# DIO-SMA.net
KiCad netlist of a schematic drawn in Altium Designer
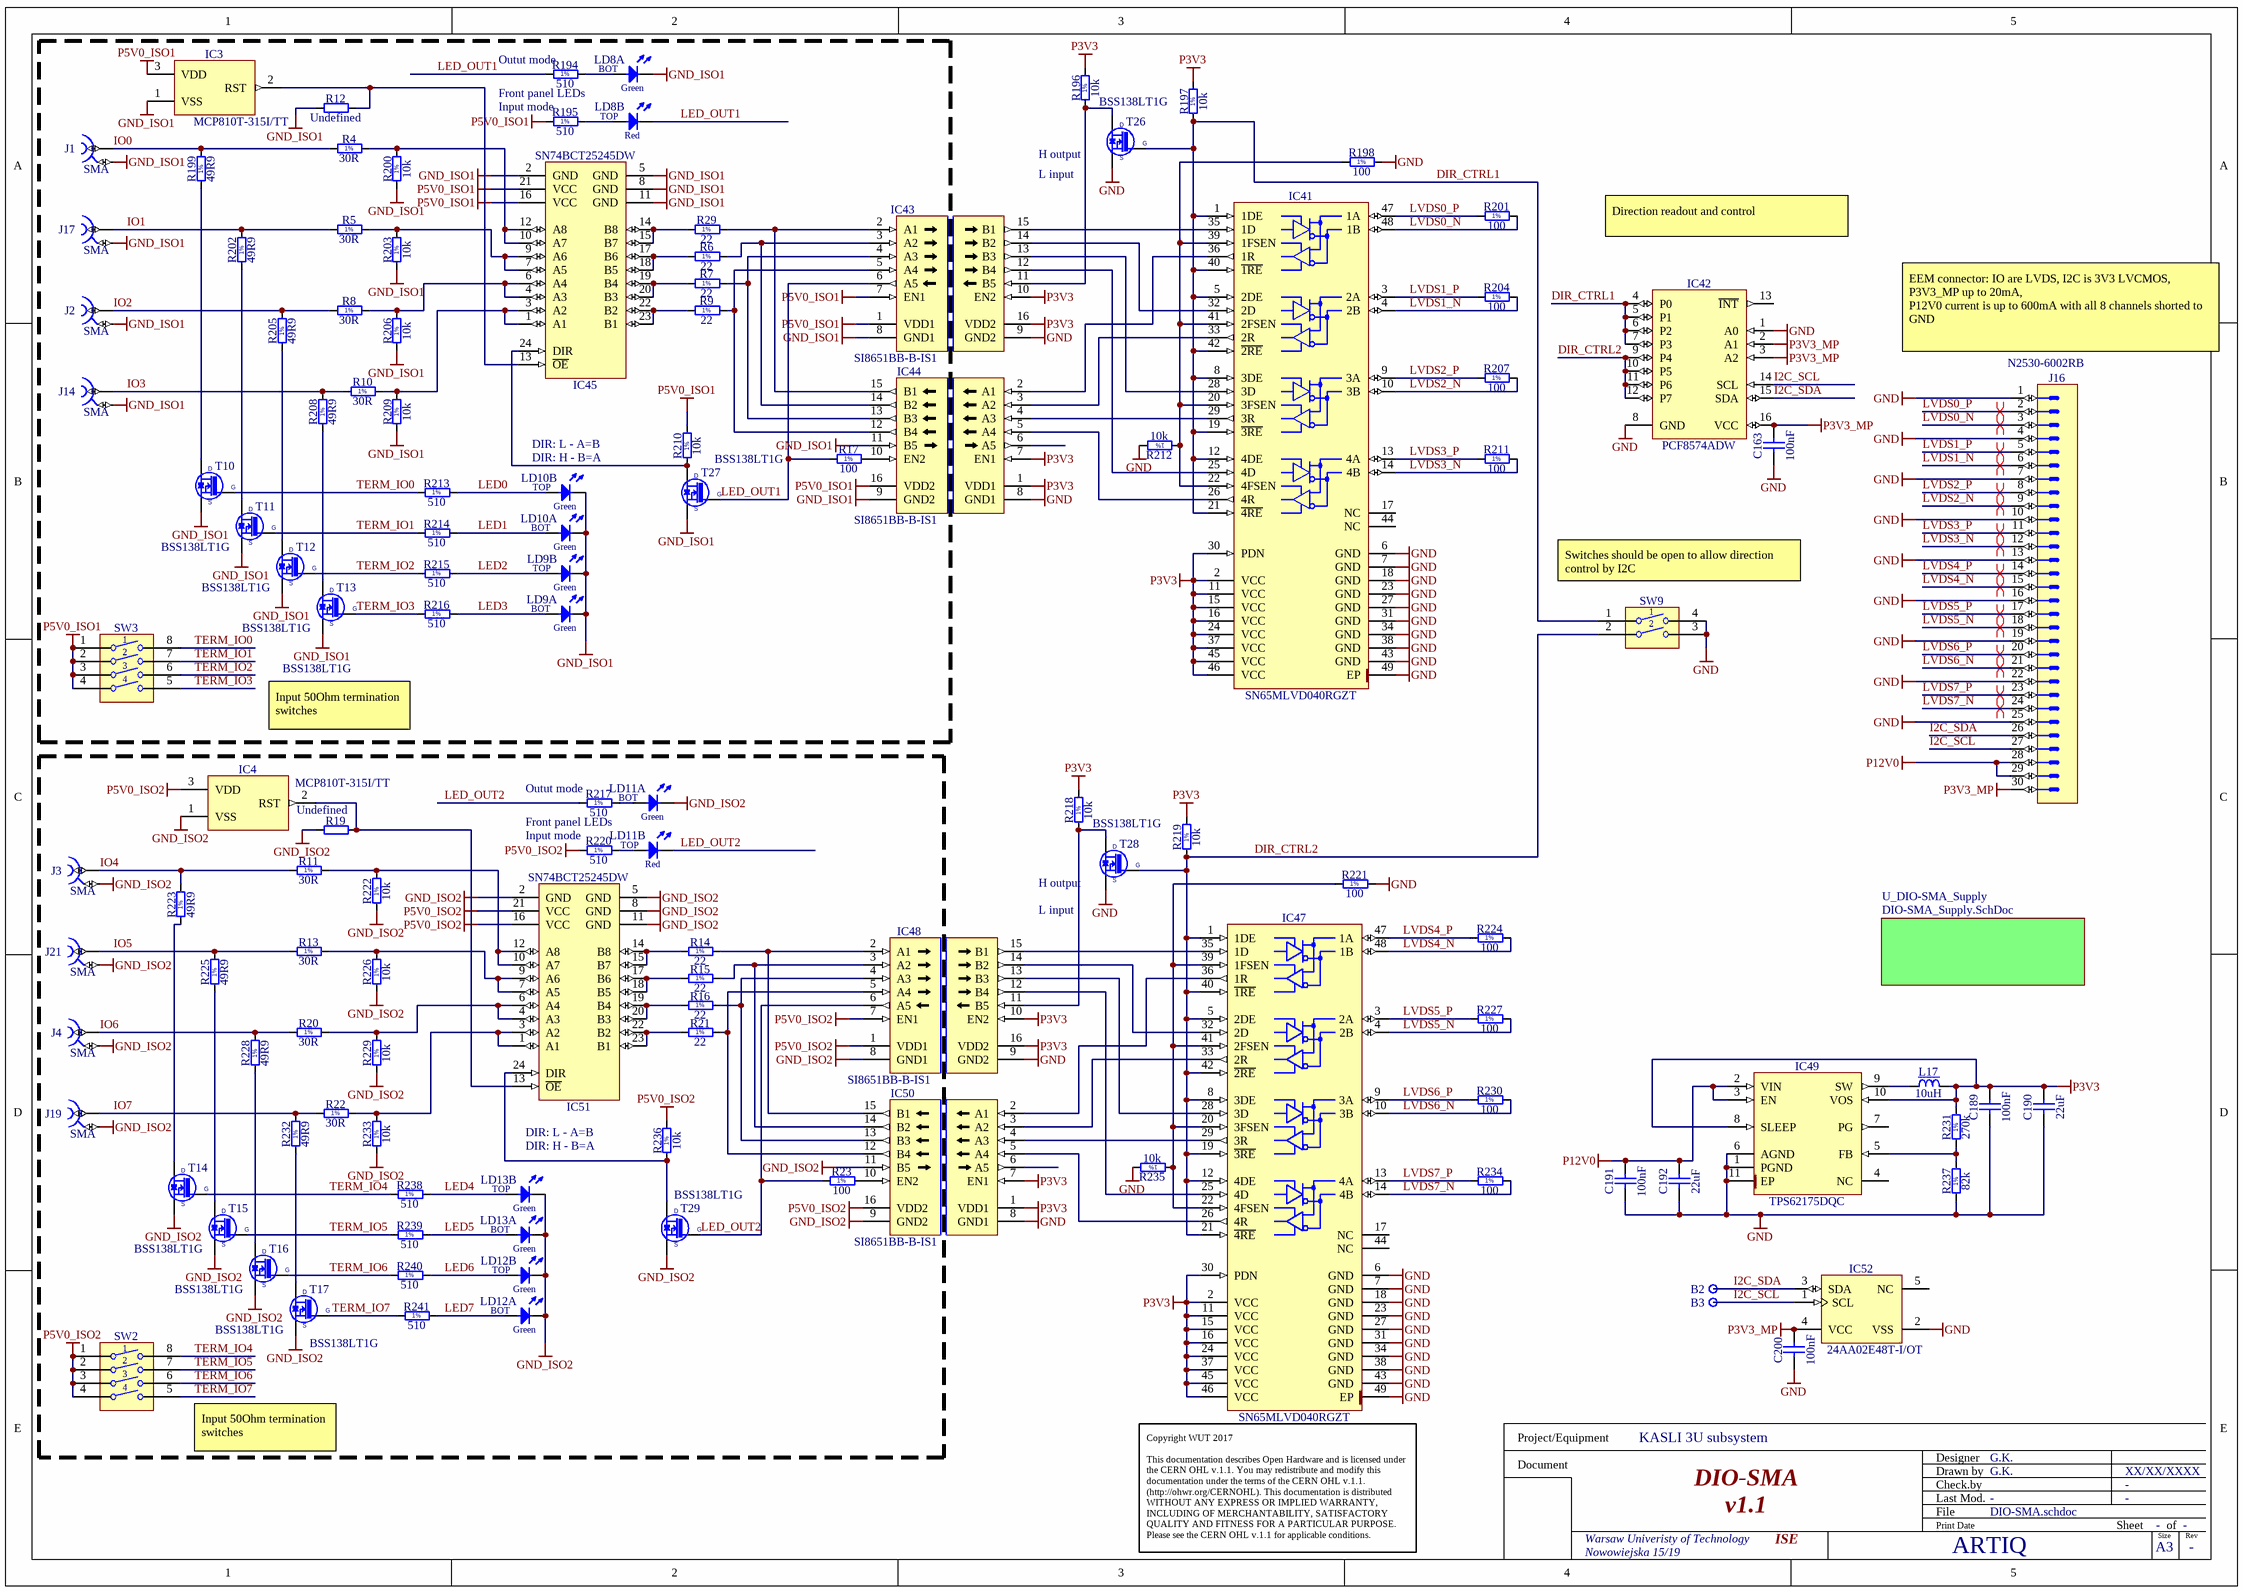
[diagram p0: DIO-SMA.schdoc]

(export (version "E")
  (design (tool "Eeschema 10.0.6"))
  (components
    (comp (ref "B2")
      (value "Plated Hole")
      (footprint "c130h60")
      (description "Single Terminal Socket")
      (fields (field (name "PART NUMBER") "PLATED_HOLE0.6_PAD1.3") (field (name "AUTHOR") "CERN DEM MR"))
      (libsource (lib "Eletro-mechanical") (part "Single Terminal Socket"))
    )
    (comp (ref "B3")
      (value "Plated Hole")
      (footprint "c130h60")
      (description "Single Terminal Socket")
      (fields (field (name "PART NUMBER") "PLATED_HOLE0.6_PAD1.3") (field (name "AUTHOR") "CERN DEM MR"))
      (libsource (lib "Eletro-mechanical") (part "Single Terminal Socket"))
    )
    (comp (ref "C163")
      (value "100nF")
      (footprint "CAPC1005X55N")
      (description "Non-polarised capacitor")
      (fields
        (field (name "PART NUMBER") "CC0402_100NF_16V_10%_X5R")
        (field (name "VOLTAGE") "16V")
        (field (name "AUTHOR") "CERN DEM JLC")
      )
      (libsource (lib "Capacitors") (part "Capacitor - non polarized"))
    )
    (comp (ref "C189")
      (value "100nF")
      (footprint "CAPC1005X55N")
      (description "Non-polarised capacitor")
      (fields
        (field (name "PART NUMBER") "CC0402_100NF_16V_10%_X5R")
        (field (name "VOLTAGE") "16V")
        (field (name "AUTHOR") "CERN DEM JLC")
      )
      (libsource (lib "Capacitors") (part "Capacitor - non polarized"))
    )
    (comp (ref "C190")
      (value "22uF")
      (footprint "CAPC2012X135N")
      (description "Non-polarised capacitor")
      (fields
        (field (name "PART NUMBER") "CC0805_22UF_16V_10%_X5R")
        (field (name "VOLTAGE") "16V")
        (field (name "AUTHOR") "CERN DEM JLC")
      )
      (libsource (lib "Capacitors") (part "Capacitor - non polarized"))
    )
    (comp (ref "C191")
      (value "100nF")
      (footprint "CAPC1005X55N")
      (description "Non-polarised capacitor")
      (fields
        (field (name "PART NUMBER") "CC0402_100NF_16V_10%_X5R")
        (field (name "VOLTAGE") "16V")
        (field (name "AUTHOR") "CERN DEM JLC")
      )
      (libsource (lib "Capacitors") (part "Capacitor - non polarized"))
    )
    (comp (ref "C192")
      (value "22uF")
      (footprint "CAPC2012X135N")
      (description "Non-polarised capacitor")
      (fields
        (field (name "PART NUMBER") "CC0805_22UF_16V_10%_X5R")
        (field (name "VOLTAGE") "16V")
        (field (name "AUTHOR") "CERN DEM JLC")
      )
      (libsource (lib "Capacitors") (part "Capacitor - non polarized"))
    )
    (comp (ref "C200")
      (value "100nF")
      (footprint "CAPC1005X55N")
      (description "Non-polarised capacitor")
      (fields
        (field (name "PART NUMBER") "CC0402_100NF_16V_10%_X5R")
        (field (name "VOLTAGE") "16V")
        (field (name "AUTHOR") "CERN DEM JLC")
      )
      (libsource (lib "Capacitors") (part "Capacitor - non polarized"))
    )
    (comp (ref "IC3")
      (value "MCP810T-315I/TT")
      (footprint "SOT95P237X112-3N")
      (description "3.075V Microcontroller Supervisory Circuit With Push-Pull Output")
      (fields (field (name "MANUFACTURER") "MICROCHIP TECHNOLOGY") (field (name "AUTHOR") "GK"))
      (libsource (lib "LIBRARY_SCH") (part "VMON_MCP810"))
    )
    (comp (ref "IC4")
      (value "MCP810T-315I/TT")
      (footprint "SOT95P237X112-3N")
      (description "3.075V Microcontroller Supervisory Circuit With Push-Pull Output")
      (fields (field (name "MANUFACTURER") "MICROCHIP TECHNOLOGY") (field (name "AUTHOR") "GK"))
      (libsource (lib "LIBRARY_SCH") (part "VMON_MCP810"))
    )
    (comp (ref "IC41")
      (value "SN65MLVD040RGZT")
      (footprint "QFN50P700X700X100-49N-S420")
      (description "4-Channel Half-Duplex M-LVDS Line Transceiver")
      (fields (field (name "MANUFACTURER") "TEXAS INSTRUMENTS") (field (name "AUTHOR") "CERN DEM JLC"))
      (libsource (lib "ICs And Semiconductors") (part "SN65MLVD040"))
    )
    (comp (ref "IC42")
      (value "PCF8574ADW")
      (footprint "SOIC127P1030X265-16N")
      (description "Remote 8-bit I/O Expander For I2C Bus")
      (fields (field (name "MANUFACTURER") "TEXAS INSTRUMENTS") (field (name "AUTHOR") "CERN DEM JLC"))
      (libsource (lib "ICs And Semiconductors") (part "PCF8574ADW"))
    )
    (comp (ref "IC43")
      (value "SI8651BB-B-IS1")
      (footprint "SOIC127P600X175-16N")
      (description "Low Power Five-Channel Digital Isolator")
      (fields (field (name "MANUFACTURER") "SILICON LABS") (field (name "AUTHOR") "CERN DEM JLC"))
      (libsource (lib "ICs And Semiconductors") (part "Si8651"))
    )
    (comp (ref "IC44")
      (value "SI8651BB-B-IS1")
      (footprint "SOIC127P600X175-16N")
      (description "Low Power Five-Channel Digital Isolator")
      (fields (field (name "MANUFACTURER") "SILICON LABS") (field (name "AUTHOR") "CERN DEM JLC"))
      (libsource (lib "") (part "Si8651_1"))
    )
    (comp (ref "IC45")
      (value "SN74BCT25245DW")
      (footprint "SOIC127P1030X265-24N")
      (description "25 Ohms Octal Bus Transceiver With 3-State Outputs")
      (fields (field (name "MANUFACTURER") "TEXAS INSTRUMENTS") (field (name "AUTHOR") "CERN DEM JLC"))
      (libsource (lib "ICs And Semiconductors") (part "7425245"))
    )
    (comp (ref "IC47")
      (value "SN65MLVD040RGZT")
      (footprint "QFN50P700X700X100-49N-S420")
      (description "4-Channel Half-Duplex M-LVDS Line Transceiver")
      (fields (field (name "MANUFACTURER") "TEXAS INSTRUMENTS") (field (name "AUTHOR") "CERN DEM JLC"))
      (libsource (lib "ICs And Semiconductors") (part "SN65MLVD040"))
    )
    (comp (ref "IC48")
      (value "SI8651BB-B-IS1")
      (footprint "SOIC127P600X175-16N")
      (description "Low Power Five-Channel Digital Isolator")
      (fields (field (name "MANUFACTURER") "SILICON LABS") (field (name "AUTHOR") "CERN DEM JLC"))
      (libsource (lib "ICs And Semiconductors") (part "Si8651"))
    )
    (comp (ref "IC49")
      (value "TPS62175DQC")
      (footprint "SON50P200X300X80-11N-R94X250")
      (description "4.75-28VDC to 1-6VDC, 500mA Step-Down Converter With Sleep Mode")
      (fields (field (name "MANUFACTURER") "TEXAS INSTRUMENTS") (field (name "AUTHOR") "CERN DEM JMW"))
      (libsource (lib "ICs And Semiconductors") (part "TPS62175"))
    )
    (comp (ref "IC50")
      (value "SI8651BB-B-IS1")
      (footprint "SOIC127P600X175-16N")
      (description "Low Power Five-Channel Digital Isolator")
      (fields (field (name "MANUFACTURER") "SILICON LABS") (field (name "AUTHOR") "CERN DEM JLC"))
      (libsource (lib "") (part "Si8651_1"))
    )
    (comp (ref "IC51")
      (value "SN74BCT25245DW")
      (footprint "SOIC127P1030X265-24N")
      (description "25 Ohms Octal Bus Transceiver With 3-State Outputs")
      (fields (field (name "MANUFACTURER") "TEXAS INSTRUMENTS") (field (name "AUTHOR") "CERN DEM JLC"))
      (libsource (lib "ICs And Semiconductors") (part "7425245"))
    )
    (comp (ref "IC52")
      (value "24AA02E48T-I/OT")
      (footprint "SOT95P280X145-5N")
      (description "1.7V-5.5V, 2K I2C Serial EEPROM With EUI-48 Node Identity")
      (fields (field (name "MANUFACTURER") "MICROCHIP TECHNOLOGY") (field (name "AUTHOR") "CERN DEM MR"))
      (libsource (lib "ICs And Semiconductors") (part "24AA02E48T-I/OT"))
    )
    (comp (ref "J1")
      (value "SMA")
      (footprint "RF249BT0050GHDW")
      (description "50 Ohm Through Hole SMA Right Angle PCB Jack")
      (fields
        (field (name "PART NUMBER") "AdamTech_RF249BT0050GHDW")
        (field (name "MANUFACTURER") "AdamTech")
        (field (name "AUTHOR") "GK")
      )
      (libsource (lib "LIBRARY_SCH") (part "CON_SMA_RF249BT0050GHDW"))
    )
    (comp (ref "J2")
      (value "SMA")
      (footprint "RF249BT0050GHDW")
      (description "50 Ohm Through Hole SMA Right Angle PCB Jack")
      (fields
        (field (name "PART NUMBER") "AdamTech_RF249BT0050GHDW")
        (field (name "MANUFACTURER") "AdamTech")
        (field (name "AUTHOR") "GK")
      )
      (libsource (lib "LIBRARY_SCH") (part "CON_SMA_RF249BT0050GHDW"))
    )
    (comp (ref "J3")
      (value "SMA")
      (footprint "RF249BT0050GHDW")
      (description "50 Ohm Through Hole SMA Right Angle PCB Jack")
      (fields
        (field (name "PART NUMBER") "AdamTech_RF249BT0050GHDW")
        (field (name "MANUFACTURER") "AdamTech")
        (field (name "AUTHOR") "GK")
      )
      (libsource (lib "LIBRARY_SCH") (part "CON_SMA_RF249BT0050GHDW"))
    )
    (comp (ref "J4")
      (value "SMA")
      (footprint "RF249BT0050GHDW")
      (description "50 Ohm Through Hole SMA Right Angle PCB Jack")
      (fields
        (field (name "PART NUMBER") "AdamTech_RF249BT0050GHDW")
        (field (name "MANUFACTURER") "AdamTech")
        (field (name "AUTHOR") "GK")
      )
      (libsource (lib "LIBRARY_SCH") (part "CON_SMA_RF249BT0050GHDW"))
    )
    (comp (ref "J14")
      (value "SMA")
      (footprint "MOLEX_73251-2120")
      (description "50 Ohm, SMA Edge Mount PCB, With Jam Nut And Lock Washer")
      (fields
        (field (name "PART NUMBER") "MOLEX_73251-2120")
        (field (name "MANUFACTURER") "MOLEX")
        (field (name "AUTHOR") "CERN DEM JLC")
      )
      (libsource (lib "LIBRARY_SCH") (part "CON_SMA_RA_SMD_73251-2120"))
    )
    (comp (ref "J16")
      (value "~")
      (footprint "3M_N2530-6002RB")
      (description "Connector 30 Male")
      (fields
        (field (name "PART NUMBER") "3M_N2530-6002RB")
        (field (name "MANUFACTURER") "3M")
        (field (name "MANUFACTURER PART NUMBER") "N2530-6002RB")
        (field (name "AUTHOR") "CERN DEM JLC")
      )
      (libsource (lib "Connectors") (part "Connector 30 Male"))
    )
    (comp (ref "J17")
      (value "SMA")
      (footprint "MOLEX_73251-2120")
      (description "50 Ohm, SMA Edge Mount PCB, With Jam Nut And Lock Washer")
      (fields
        (field (name "PART NUMBER") "MOLEX_73251-2120")
        (field (name "MANUFACTURER") "MOLEX")
        (field (name "AUTHOR") "CERN DEM JLC")
      )
      (libsource (lib "LIBRARY_SCH") (part "CON_SMA_RA_SMD_73251-2120"))
    )
    (comp (ref "J19")
      (value "SMA")
      (footprint "MOLEX_73251-2120")
      (description "50 Ohm, SMA Edge Mount PCB, With Jam Nut And Lock Washer")
      (fields
        (field (name "PART NUMBER") "MOLEX_73251-2120")
        (field (name "MANUFACTURER") "MOLEX")
        (field (name "AUTHOR") "CERN DEM JLC")
      )
      (libsource (lib "LIBRARY_SCH") (part "CON_SMA_RA_SMD_73251-2120"))
    )
    (comp (ref "J21")
      (value "SMA")
      (footprint "MOLEX_73251-2120")
      (description "50 Ohm, SMA Edge Mount PCB, With Jam Nut And Lock Washer")
      (fields
        (field (name "PART NUMBER") "MOLEX_73251-2120")
        (field (name "MANUFACTURER") "MOLEX")
        (field (name "AUTHOR") "CERN DEM JLC")
      )
      (libsource (lib "LIBRARY_SCH") (part "CON_SMA_RA_SMD_73251-2120"))
    )
    (comp (ref "L17")
      (value "10uH")
      (footprint "IND_MURATA-PS_8400")
      (description "Inductor With Core")
      (fields
        (field (name "PART NUMBER") "IND_10UH_10%_MURATA-PS_8400")
        (field (name "POWER") "950mA")
        (field (name "AUTHOR") "CERN DEM JLC")
      )
      (libsource (lib "Inductors & Transformers") (part "Inductor With Magnetic core"))
    )
    (comp (ref "LD8")
      (value "Red/Green")
      (footprint "LED_DIALIGHT_571-0112F")
      (description "2x LED  Botom Green, Top Red")
      (fields
        (field (name "PART NUMBER") "LED_DIALIGHT_571-0112F")
        (field (name "MANUFACTURER") "DIALIGHT")
        (field (name "AUTHOR") "CERN DEM JLC")
      )
      (libsource (lib "ICs And Semiconductors") (part "LED x2 G-1C2A-BOT_R-3C4A-TOP"))
    )
    (comp (ref "LD9")
      (value "Green/Green")
      (footprint "LED_DIALIGHT_571-0122F")
      (description "LED x2 Green 1C2A-BOT_3C4A-TOP")
      (fields
        (field (name "PART NUMBER") "LED_DIALIGHT_571-0122F")
        (field (name "MANUFACTURER") "DIALIGHT")
        (field (name "AUTHOR") "CERN DEM JLC")
      )
      (libsource (lib "ICs And Semiconductors") (part "LED x2 Green 1C2A-BOT_3C4A-TOP"))
    )
    (comp (ref "LD10")
      (value "Green/Green")
      (footprint "LED_DIALIGHT_571-0122F")
      (description "LED x2 Green 1C2A-BOT_3C4A-TOP")
      (fields
        (field (name "PART NUMBER") "LED_DIALIGHT_571-0122F")
        (field (name "MANUFACTURER") "DIALIGHT")
        (field (name "AUTHOR") "CERN DEM JLC")
      )
      (libsource (lib "ICs And Semiconductors") (part "LED x2 Green 1C2A-BOT_3C4A-TOP"))
    )
    (comp (ref "LD11")
      (value "Red/Green")
      (footprint "LED_DIALIGHT_571-0112F")
      (description "2x LED  Botom Green, Top Red")
      (fields
        (field (name "PART NUMBER") "LED_DIALIGHT_571-0112F")
        (field (name "MANUFACTURER") "DIALIGHT")
        (field (name "AUTHOR") "CERN DEM JLC")
      )
      (libsource (lib "ICs And Semiconductors") (part "LED x2 G-1C2A-BOT_R-3C4A-TOP"))
    )
    (comp (ref "LD12")
      (value "Green/Green")
      (footprint "LED_DIALIGHT_571-0122F")
      (description "LED x2 Green 1C2A-BOT_3C4A-TOP")
      (fields
        (field (name "PART NUMBER") "LED_DIALIGHT_571-0122F")
        (field (name "MANUFACTURER") "DIALIGHT")
        (field (name "AUTHOR") "CERN DEM JLC")
      )
      (libsource (lib "ICs And Semiconductors") (part "LED x2 Green 1C2A-BOT_3C4A-TOP"))
    )
    (comp (ref "LD13")
      (value "Green/Green")
      (footprint "LED_DIALIGHT_571-0122F")
      (description "LED x2 Green 1C2A-BOT_3C4A-TOP")
      (fields
        (field (name "PART NUMBER") "LED_DIALIGHT_571-0122F")
        (field (name "MANUFACTURER") "DIALIGHT")
        (field (name "AUTHOR") "CERN DEM JLC")
      )
      (libsource (lib "ICs And Semiconductors") (part "LED x2 Green 1C2A-BOT_3C4A-TOP"))
    )
    (comp (ref "R4")
      (value "30R")
      (footprint "RESC3225X70N")
      (description "Resistor - 5%")
      (fields
        (field (name "PART NUMBER") "R1210_30R_5%_0.5W_200ppm")
        (field (name "POWER") "0.5W")
        (field (name "AUTHOR") "CERN DEM JMW")
      )
      (libsource (lib "LIBRARY_SCH") (part "R1210_30R_5%_0.5W_200PPM"))
    )
    (comp (ref "R5")
      (value "30R")
      (footprint "RESC3225X70N")
      (description "Resistor - 5%")
      (fields
        (field (name "PART NUMBER") "R1210_30R_5%_0.5W_200ppm")
        (field (name "POWER") "0.5W")
        (field (name "AUTHOR") "CERN DEM JMW")
      )
      (libsource (lib "LIBRARY_SCH") (part "R1210_30R_5%_0.5W_200PPM"))
    )
    (comp (ref "R6")
      (value "22")
      (footprint "RESC1005X40N")
      (description "Resistor - 1%")
      (fields
        (field (name "PART NUMBER") "R0402_22R_1%_0.0625W_100PPM")
        (field (name "POWER") "0.0625W")
        (field (name "AUTHOR") "CERN DEM JLC")
      )
      (libsource (lib "Resistors") (part "Resistor - 1%"))
    )
    (comp (ref "R7")
      (value "22")
      (footprint "RESC1005X40N")
      (description "Resistor - 1%")
      (fields
        (field (name "PART NUMBER") "R0402_22R_1%_0.0625W_100PPM")
        (field (name "POWER") "0.0625W")
        (field (name "AUTHOR") "CERN DEM JLC")
      )
      (libsource (lib "Resistors") (part "Resistor - 1%"))
    )
    (comp (ref "R8")
      (value "30R")
      (footprint "RESC3225X70N")
      (description "Resistor - 5%")
      (fields
        (field (name "PART NUMBER") "R1210_30R_5%_0.5W_200ppm")
        (field (name "POWER") "0.5W")
        (field (name "AUTHOR") "CERN DEM JMW")
      )
      (libsource (lib "LIBRARY_SCH") (part "R1210_30R_5%_0.5W_200PPM"))
    )
    (comp (ref "R9")
      (value "22")
      (footprint "RESC1005X40N")
      (description "Resistor - 1%")
      (fields
        (field (name "PART NUMBER") "R0402_22R_1%_0.0625W_100PPM")
        (field (name "POWER") "0.0625W")
        (field (name "AUTHOR") "CERN DEM JLC")
      )
      (libsource (lib "Resistors") (part "Resistor - 1%"))
    )
    (comp (ref "R10")
      (value "30R")
      (footprint "RESC3225X70N")
      (description "Resistor - 5%")
      (fields
        (field (name "PART NUMBER") "R1210_30R_5%_0.5W_200ppm")
        (field (name "POWER") "0.5W")
        (field (name "AUTHOR") "CERN DEM JMW")
      )
      (libsource (lib "LIBRARY_SCH") (part "R1210_30R_5%_0.5W_200PPM"))
    )
    (comp (ref "R11")
      (value "30R")
      (footprint "RESC3225X70N")
      (description "Resistor - 5%")
      (fields
        (field (name "PART NUMBER") "R1210_30R_5%_0.5W_200ppm")
        (field (name "POWER") "0.5W")
        (field (name "AUTHOR") "CERN DEM JMW")
      )
      (libsource (lib "LIBRARY_SCH") (part "R1210_30R_5%_0.5W_200PPM"))
    )
    (comp (ref "R12")
      (value "Undefined")
      (footprint "RESC1005X40N")
      (description "Resistor")
      (fields (field (name "PART NUMBER") "R0402_NO-VALUE") (field (name "AUTHOR") "CERN DEM JLC"))
      (libsource (lib "Resistors") (part "Resistor"))
    )
    (comp (ref "R13")
      (value "30R")
      (footprint "RESC3225X70N")
      (description "Resistor - 5%")
      (fields
        (field (name "PART NUMBER") "R1210_30R_5%_0.5W_200ppm")
        (field (name "POWER") "0.5W")
        (field (name "AUTHOR") "CERN DEM JMW")
      )
      (libsource (lib "LIBRARY_SCH") (part "R1210_30R_5%_0.5W_200PPM"))
    )
    (comp (ref "R14")
      (value "22")
      (footprint "RESC1005X40N")
      (description "Resistor - 1%")
      (fields
        (field (name "PART NUMBER") "R0402_22R_1%_0.0625W_100PPM")
        (field (name "POWER") "0.0625W")
        (field (name "AUTHOR") "CERN DEM JLC")
      )
      (libsource (lib "Resistors") (part "Resistor - 1%"))
    )
    (comp (ref "R15")
      (value "22")
      (footprint "RESC1005X40N")
      (description "Resistor - 1%")
      (fields
        (field (name "PART NUMBER") "R0402_22R_1%_0.0625W_100PPM")
        (field (name "POWER") "0.0625W")
        (field (name "AUTHOR") "CERN DEM JLC")
      )
      (libsource (lib "Resistors") (part "Resistor - 1%"))
    )
    (comp (ref "R16")
      (value "22")
      (footprint "RESC1005X40N")
      (description "Resistor - 1%")
      (fields
        (field (name "PART NUMBER") "R0402_22R_1%_0.0625W_100PPM")
        (field (name "POWER") "0.0625W")
        (field (name "AUTHOR") "CERN DEM JLC")
      )
      (libsource (lib "Resistors") (part "Resistor - 1%"))
    )
    (comp (ref "R17")
      (value "100")
      (footprint "RESC1005X40N")
      (description "Resistor - 1%")
      (fields
        (field (name "PART NUMBER") "R0402_100R_1%_0.1W_100PPM")
        (field (name "POWER") "0.1W")
        (field (name "AUTHOR") "CERN DEM JLC")
      )
      (libsource (lib "Resistors") (part "Resistor - 1%"))
    )
    (comp (ref "R19")
      (value "Undefined")
      (footprint "RESC1005X40N")
      (description "Resistor")
      (fields (field (name "PART NUMBER") "R0402_NO-VALUE") (field (name "AUTHOR") "CERN DEM JLC"))
      (libsource (lib "Resistors") (part "Resistor"))
    )
    (comp (ref "R20")
      (value "30R")
      (footprint "RESC3225X70N")
      (description "Resistor - 5%")
      (fields
        (field (name "PART NUMBER") "R1210_30R_5%_0.5W_200ppm")
        (field (name "POWER") "0.5W")
        (field (name "AUTHOR") "CERN DEM JMW")
      )
      (libsource (lib "LIBRARY_SCH") (part "R1210_30R_5%_0.5W_200PPM"))
    )
    (comp (ref "R21")
      (value "22")
      (footprint "RESC1005X40N")
      (description "Resistor - 1%")
      (fields
        (field (name "PART NUMBER") "R0402_22R_1%_0.0625W_100PPM")
        (field (name "POWER") "0.0625W")
        (field (name "AUTHOR") "CERN DEM JLC")
      )
      (libsource (lib "Resistors") (part "Resistor - 1%"))
    )
    (comp (ref "R22")
      (value "30R")
      (footprint "RESC3225X70N")
      (description "Resistor - 5%")
      (fields
        (field (name "PART NUMBER") "R1210_30R_5%_0.5W_200ppm")
        (field (name "POWER") "0.5W")
        (field (name "AUTHOR") "CERN DEM JMW")
      )
      (libsource (lib "LIBRARY_SCH") (part "R1210_30R_5%_0.5W_200PPM"))
    )
    (comp (ref "R23")
      (value "100")
      (footprint "RESC1005X40N")
      (description "Resistor - 1%")
      (fields
        (field (name "PART NUMBER") "R0402_100R_1%_0.1W_100PPM")
        (field (name "POWER") "0.1W")
        (field (name "AUTHOR") "CERN DEM JLC")
      )
      (libsource (lib "Resistors") (part "Resistor - 1%"))
    )
    (comp (ref "R29")
      (value "22")
      (footprint "RESC1005X40N")
      (description "Resistor - 1%")
      (fields
        (field (name "PART NUMBER") "R0402_22R_1%_0.0625W_100PPM")
        (field (name "POWER") "0.0625W")
        (field (name "AUTHOR") "CERN DEM JLC")
      )
      (libsource (lib "Resistors") (part "Resistor - 1%"))
    )
    (comp (ref "R194")
      (value "510")
      (footprint "RESC1005X40N")
      (description "Resistor - 1%")
      (fields
        (field (name "PART NUMBER") "R0402_510R_1%_0.0625W_100PPM")
        (field (name "POWER") "0.0625W")
        (field (name "AUTHOR") "CERN DEM JLC")
      )
      (libsource (lib "Resistors") (part "Resistor - 1%"))
    )
    (comp (ref "R195")
      (value "510")
      (footprint "RESC1005X40N")
      (description "Resistor - 1%")
      (fields
        (field (name "PART NUMBER") "R0402_510R_1%_0.0625W_100PPM")
        (field (name "POWER") "0.0625W")
        (field (name "AUTHOR") "CERN DEM JLC")
      )
      (libsource (lib "Resistors") (part "Resistor - 1%"))
    )
    (comp (ref "R196")
      (value "10k")
      (footprint "RESC1005X40N")
      (description "Resistor - 1%")
      (fields
        (field (name "PART NUMBER") "R0402_10K_1%_0.0625W_100PPM")
        (field (name "POWER") "0.0625W")
        (field (name "AUTHOR") "CERN DEM JLC")
      )
      (libsource (lib "Resistors") (part "Resistor - 1%"))
    )
    (comp (ref "R197")
      (value "10k")
      (footprint "RESC1005X40N")
      (description "Resistor - 1%")
      (fields
        (field (name "PART NUMBER") "R0402_10K_1%_0.0625W_100PPM")
        (field (name "POWER") "0.0625W")
        (field (name "AUTHOR") "CERN DEM JLC")
      )
      (libsource (lib "Resistors") (part "Resistor - 1%"))
    )
    (comp (ref "R198")
      (value "100")
      (footprint "RESC1005X40N")
      (description "Resistor - 1%")
      (fields
        (field (name "PART NUMBER") "R0402_100R_1%_0.1W_100PPM")
        (field (name "POWER") "0.1W")
        (field (name "AUTHOR") "CERN DEM JLC")
      )
      (libsource (lib "Resistors") (part "Resistor - 1%"))
    )
    (comp (ref "R199")
      (value "49R9")
      (footprint "RESC3225X70N")
      (description "Resistor - 1%")
      (fields
        (field (name "PART NUMBER") "R1210_49R9_1%_0.5W_100PPM_VISHAY_CRCW")
        (field (name "POWER") "0.5W")
        (field (name "AUTHOR") "CERN DEM JMW")
      )
      (libsource (lib "Resistors") (part "Resistor - 1%"))
    )
    (comp (ref "R200")
      (value "10k")
      (footprint "RESC1005X40N")
      (description "Resistor - 1%")
      (fields
        (field (name "PART NUMBER") "R0402_10K_1%_0.0625W_100PPM")
        (field (name "POWER") "0.0625W")
        (field (name "AUTHOR") "CERN DEM JLC")
      )
      (libsource (lib "Resistors") (part "Resistor - 1%"))
    )
    (comp (ref "R201")
      (value "100")
      (footprint "RESC1005X40N")
      (description "Resistor - 1%")
      (fields
        (field (name "PART NUMBER") "R0402_100R_1%_0.1W_100PPM")
        (field (name "POWER") "0.1W")
        (field (name "AUTHOR") "CERN DEM JLC")
      )
      (libsource (lib "Resistors") (part "Resistor - 1%"))
    )
    (comp (ref "R202")
      (value "49R9")
      (footprint "RESC3225X70N")
      (description "Resistor - 1%")
      (fields
        (field (name "PART NUMBER") "R1210_49R9_1%_0.5W_100PPM_VISHAY_CRCW")
        (field (name "POWER") "0.5W")
        (field (name "AUTHOR") "CERN DEM JMW")
      )
      (libsource (lib "Resistors") (part "Resistor - 1%"))
    )
    (comp (ref "R203")
      (value "10k")
      (footprint "RESC1005X40N")
      (description "Resistor - 1%")
      (fields
        (field (name "PART NUMBER") "R0402_10K_1%_0.0625W_100PPM")
        (field (name "POWER") "0.0625W")
        (field (name "AUTHOR") "CERN DEM JLC")
      )
      (libsource (lib "Resistors") (part "Resistor - 1%"))
    )
    (comp (ref "R204")
      (value "100")
      (footprint "RESC1005X40N")
      (description "Resistor - 1%")
      (fields
        (field (name "PART NUMBER") "R0402_100R_1%_0.1W_100PPM")
        (field (name "POWER") "0.1W")
        (field (name "AUTHOR") "CERN DEM JLC")
      )
      (libsource (lib "Resistors") (part "Resistor - 1%"))
    )
    (comp (ref "R205")
      (value "49R9")
      (footprint "RESC3225X70N")
      (description "Resistor - 1%")
      (fields
        (field (name "PART NUMBER") "R1210_49R9_1%_0.5W_100PPM_VISHAY_CRCW")
        (field (name "POWER") "0.5W")
        (field (name "AUTHOR") "CERN DEM JMW")
      )
      (libsource (lib "Resistors") (part "Resistor - 1%"))
    )
    (comp (ref "R206")
      (value "10k")
      (footprint "RESC1005X40N")
      (description "Resistor - 1%")
      (fields
        (field (name "PART NUMBER") "R0402_10K_1%_0.0625W_100PPM")
        (field (name "POWER") "0.0625W")
        (field (name "AUTHOR") "CERN DEM JLC")
      )
      (libsource (lib "Resistors") (part "Resistor - 1%"))
    )
    (comp (ref "R207")
      (value "100")
      (footprint "RESC1005X40N")
      (description "Resistor - 1%")
      (fields
        (field (name "PART NUMBER") "R0402_100R_1%_0.1W_100PPM")
        (field (name "POWER") "0.1W")
        (field (name "AUTHOR") "CERN DEM JLC")
      )
      (libsource (lib "Resistors") (part "Resistor - 1%"))
    )
    (comp (ref "R208")
      (value "49R9")
      (footprint "RESC3225X70N")
      (description "Resistor - 1%")
      (fields
        (field (name "PART NUMBER") "R1210_49R9_1%_0.5W_100PPM_VISHAY_CRCW")
        (field (name "POWER") "0.5W")
        (field (name "AUTHOR") "CERN DEM JMW")
      )
      (libsource (lib "Resistors") (part "Resistor - 1%"))
    )
    (comp (ref "R209")
      (value "10k")
      (footprint "RESC1005X40N")
      (description "Resistor - 1%")
      (fields
        (field (name "PART NUMBER") "R0402_10K_1%_0.0625W_100PPM")
        (field (name "POWER") "0.0625W")
        (field (name "AUTHOR") "CERN DEM JLC")
      )
      (libsource (lib "Resistors") (part "Resistor - 1%"))
    )
    (comp (ref "R210")
      (value "10k")
      (footprint "RESC1005X40N")
      (description "Resistor - 1%")
      (fields
        (field (name "PART NUMBER") "R0402_10K_1%_0.0625W_100PPM")
        (field (name "POWER") "0.0625W")
        (field (name "AUTHOR") "CERN DEM JLC")
      )
      (libsource (lib "Resistors") (part "Resistor - 1%"))
    )
    (comp (ref "R211")
      (value "100")
      (footprint "RESC1005X40N")
      (description "Resistor - 1%")
      (fields
        (field (name "PART NUMBER") "R0402_100R_1%_0.1W_100PPM")
        (field (name "POWER") "0.1W")
        (field (name "AUTHOR") "CERN DEM JLC")
      )
      (libsource (lib "Resistors") (part "Resistor - 1%"))
    )
    (comp (ref "R212")
      (value "10k")
      (footprint "RESC1005X40N")
      (description "Resistor - 1%")
      (fields
        (field (name "PART NUMBER") "R0402_10K_1%_0.0625W_100PPM")
        (field (name "POWER") "0.0625W")
        (field (name "AUTHOR") "CERN DEM JLC")
      )
      (libsource (lib "Resistors") (part "Resistor - 1%"))
    )
    (comp (ref "R213")
      (value "510")
      (footprint "RESC1005X40N")
      (description "Resistor - 1%")
      (fields
        (field (name "PART NUMBER") "R0402_510R_1%_0.0625W_100PPM")
        (field (name "POWER") "0.0625W")
        (field (name "AUTHOR") "CERN DEM JLC")
      )
      (libsource (lib "Resistors") (part "Resistor - 1%"))
    )
    (comp (ref "R214")
      (value "510")
      (footprint "RESC1005X40N")
      (description "Resistor - 1%")
      (fields
        (field (name "PART NUMBER") "R0402_510R_1%_0.0625W_100PPM")
        (field (name "POWER") "0.0625W")
        (field (name "AUTHOR") "CERN DEM JLC")
      )
      (libsource (lib "Resistors") (part "Resistor - 1%"))
    )
    (comp (ref "R215")
      (value "510")
      (footprint "RESC1005X40N")
      (description "Resistor - 1%")
      (fields
        (field (name "PART NUMBER") "R0402_510R_1%_0.0625W_100PPM")
        (field (name "POWER") "0.0625W")
        (field (name "AUTHOR") "CERN DEM JLC")
      )
      (libsource (lib "Resistors") (part "Resistor - 1%"))
    )
    (comp (ref "R216")
      (value "510")
      (footprint "RESC1005X40N")
      (description "Resistor - 1%")
      (fields
        (field (name "PART NUMBER") "R0402_510R_1%_0.0625W_100PPM")
        (field (name "POWER") "0.0625W")
        (field (name "AUTHOR") "CERN DEM JLC")
      )
      (libsource (lib "Resistors") (part "Resistor - 1%"))
    )
    (comp (ref "R217")
      (value "510")
      (footprint "RESC1005X40N")
      (description "Resistor - 1%")
      (fields
        (field (name "PART NUMBER") "R0402_510R_1%_0.0625W_100PPM")
        (field (name "POWER") "0.0625W")
        (field (name "AUTHOR") "CERN DEM JLC")
      )
      (libsource (lib "Resistors") (part "Resistor - 1%"))
    )
    (comp (ref "R218")
      (value "10k")
      (footprint "RESC1005X40N")
      (description "Resistor - 1%")
      (fields
        (field (name "PART NUMBER") "R0402_10K_1%_0.0625W_100PPM")
        (field (name "POWER") "0.0625W")
        (field (name "AUTHOR") "CERN DEM JLC")
      )
      (libsource (lib "Resistors") (part "Resistor - 1%"))
    )
    (comp (ref "R219")
      (value "10k")
      (footprint "RESC1005X40N")
      (description "Resistor - 1%")
      (fields
        (field (name "PART NUMBER") "R0402_10K_1%_0.0625W_100PPM")
        (field (name "POWER") "0.0625W")
        (field (name "AUTHOR") "CERN DEM JLC")
      )
      (libsource (lib "Resistors") (part "Resistor - 1%"))
    )
    (comp (ref "R220")
      (value "510")
      (footprint "RESC1005X40N")
      (description "Resistor - 1%")
      (fields
        (field (name "PART NUMBER") "R0402_510R_1%_0.0625W_100PPM")
        (field (name "POWER") "0.0625W")
        (field (name "AUTHOR") "CERN DEM JLC")
      )
      (libsource (lib "Resistors") (part "Resistor - 1%"))
    )
    (comp (ref "R221")
      (value "100")
      (footprint "RESC1005X40N")
      (description "Resistor - 1%")
      (fields
        (field (name "PART NUMBER") "R0402_100R_1%_0.1W_100PPM")
        (field (name "POWER") "0.1W")
        (field (name "AUTHOR") "CERN DEM JLC")
      )
      (libsource (lib "Resistors") (part "Resistor - 1%"))
    )
    (comp (ref "R222")
      (value "10k")
      (footprint "RESC1005X40N")
      (description "Resistor - 1%")
      (fields
        (field (name "PART NUMBER") "R0402_10K_1%_0.0625W_100PPM")
        (field (name "POWER") "0.0625W")
        (field (name "AUTHOR") "CERN DEM JLC")
      )
      (libsource (lib "Resistors") (part "Resistor - 1%"))
    )
    (comp (ref "R223")
      (value "49R9")
      (footprint "RESC3225X70N")
      (description "Resistor - 1%")
      (fields
        (field (name "PART NUMBER") "R1210_49R9_1%_0.5W_100PPM_VISHAY_CRCW")
        (field (name "POWER") "0.5W")
        (field (name "AUTHOR") "CERN DEM JMW")
      )
      (libsource (lib "Resistors") (part "Resistor - 1%"))
    )
    (comp (ref "R224")
      (value "100")
      (footprint "RESC1005X40N")
      (description "Resistor - 1%")
      (fields
        (field (name "PART NUMBER") "R0402_100R_1%_0.1W_100PPM")
        (field (name "POWER") "0.1W")
        (field (name "AUTHOR") "CERN DEM JLC")
      )
      (libsource (lib "Resistors") (part "Resistor - 1%"))
    )
    (comp (ref "R225")
      (value "49R9")
      (footprint "RESC3225X70N")
      (description "Resistor - 1%")
      (fields
        (field (name "PART NUMBER") "R1210_49R9_1%_0.5W_100PPM_VISHAY_CRCW")
        (field (name "POWER") "0.5W")
        (field (name "AUTHOR") "CERN DEM JMW")
      )
      (libsource (lib "Resistors") (part "Resistor - 1%"))
    )
    (comp (ref "R226")
      (value "10k")
      (footprint "RESC1005X40N")
      (description "Resistor - 1%")
      (fields
        (field (name "PART NUMBER") "R0402_10K_1%_0.0625W_100PPM")
        (field (name "POWER") "0.0625W")
        (field (name "AUTHOR") "CERN DEM JLC")
      )
      (libsource (lib "Resistors") (part "Resistor - 1%"))
    )
    (comp (ref "R227")
      (value "100")
      (footprint "RESC1005X40N")
      (description "Resistor - 1%")
      (fields
        (field (name "PART NUMBER") "R0402_100R_1%_0.1W_100PPM")
        (field (name "POWER") "0.1W")
        (field (name "AUTHOR") "CERN DEM JLC")
      )
      (libsource (lib "Resistors") (part "Resistor - 1%"))
    )
    (comp (ref "R228")
      (value "49R9")
      (footprint "RESC3225X70N")
      (description "Resistor - 1%")
      (fields
        (field (name "PART NUMBER") "R1210_49R9_1%_0.5W_100PPM_VISHAY_CRCW")
        (field (name "POWER") "0.5W")
        (field (name "AUTHOR") "CERN DEM JMW")
      )
      (libsource (lib "Resistors") (part "Resistor - 1%"))
    )
    (comp (ref "R229")
      (value "10k")
      (footprint "RESC1005X40N")
      (description "Resistor - 1%")
      (fields
        (field (name "PART NUMBER") "R0402_10K_1%_0.0625W_100PPM")
        (field (name "POWER") "0.0625W")
        (field (name "AUTHOR") "CERN DEM JLC")
      )
      (libsource (lib "Resistors") (part "Resistor - 1%"))
    )
    (comp (ref "R230")
      (value "100")
      (footprint "RESC1005X40N")
      (description "Resistor - 1%")
      (fields
        (field (name "PART NUMBER") "R0402_100R_1%_0.1W_100PPM")
        (field (name "POWER") "0.1W")
        (field (name "AUTHOR") "CERN DEM JLC")
      )
      (libsource (lib "Resistors") (part "Resistor - 1%"))
    )
    (comp (ref "R231")
      (value "270k")
      (footprint "RESC1608X55N")
      (description "Resistor - 1%")
      (fields
        (field (name "PART NUMBER") "R0603_270K_1%_0.1W_100PPM")
        (field (name "POWER") "0.1W")
        (field (name "AUTHOR") "CERN DEM JLC")
      )
      (libsource (lib "Resistors") (part "Resistor - 1%"))
    )
    (comp (ref "R232")
      (value "49R9")
      (footprint "RESC3225X70N")
      (description "Resistor - 1%")
      (fields
        (field (name "PART NUMBER") "R1210_49R9_1%_0.5W_100PPM_VISHAY_CRCW")
        (field (name "POWER") "0.5W")
        (field (name "AUTHOR") "CERN DEM JMW")
      )
      (libsource (lib "Resistors") (part "Resistor - 1%"))
    )
    (comp (ref "R233")
      (value "10k")
      (footprint "RESC1005X40N")
      (description "Resistor - 1%")
      (fields
        (field (name "PART NUMBER") "R0402_10K_1%_0.0625W_100PPM")
        (field (name "POWER") "0.0625W")
        (field (name "AUTHOR") "CERN DEM JLC")
      )
      (libsource (lib "Resistors") (part "Resistor - 1%"))
    )
    (comp (ref "R234")
      (value "100")
      (footprint "RESC1005X40N")
      (description "Resistor - 1%")
      (fields
        (field (name "PART NUMBER") "R0402_100R_1%_0.1W_100PPM")
        (field (name "POWER") "0.1W")
        (field (name "AUTHOR") "CERN DEM JLC")
      )
      (libsource (lib "Resistors") (part "Resistor - 1%"))
    )
    (comp (ref "R235")
      (value "10k")
      (footprint "RESC1005X40N")
      (description "Resistor - 1%")
      (fields
        (field (name "PART NUMBER") "R0402_10K_1%_0.0625W_100PPM")
        (field (name "POWER") "0.0625W")
        (field (name "AUTHOR") "CERN DEM JLC")
      )
      (libsource (lib "Resistors") (part "Resistor - 1%"))
    )
    (comp (ref "R236")
      (value "10k")
      (footprint "RESC1005X40N")
      (description "Resistor - 1%")
      (fields
        (field (name "PART NUMBER") "R0402_10K_1%_0.0625W_100PPM")
        (field (name "POWER") "0.0625W")
        (field (name "AUTHOR") "CERN DEM JLC")
      )
      (libsource (lib "Resistors") (part "Resistor - 1%"))
    )
    (comp (ref "R237")
      (value "82k")
      (footprint "RESC1608X55N")
      (description "Resistor - 1%")
      (fields
        (field (name "PART NUMBER") "R0603_82K_1%_0.1W_100PPM")
        (field (name "POWER") "0.1W")
        (field (name "AUTHOR") "CERN DEM JLC")
      )
      (libsource (lib "Resistors") (part "Resistor - 1%"))
    )
    (comp (ref "R238")
      (value "510")
      (footprint "RESC1005X40N")
      (description "Resistor - 1%")
      (fields
        (field (name "PART NUMBER") "R0402_510R_1%_0.0625W_100PPM")
        (field (name "POWER") "0.0625W")
        (field (name "AUTHOR") "CERN DEM JLC")
      )
      (libsource (lib "Resistors") (part "Resistor - 1%"))
    )
    (comp (ref "R239")
      (value "510")
      (footprint "RESC1005X40N")
      (description "Resistor - 1%")
      (fields
        (field (name "PART NUMBER") "R0402_510R_1%_0.0625W_100PPM")
        (field (name "POWER") "0.0625W")
        (field (name "AUTHOR") "CERN DEM JLC")
      )
      (libsource (lib "Resistors") (part "Resistor - 1%"))
    )
    (comp (ref "R240")
      (value "510")
      (footprint "RESC1005X40N")
      (description "Resistor - 1%")
      (fields
        (field (name "PART NUMBER") "R0402_510R_1%_0.0625W_100PPM")
        (field (name "POWER") "0.0625W")
        (field (name "AUTHOR") "CERN DEM JLC")
      )
      (libsource (lib "Resistors") (part "Resistor - 1%"))
    )
    (comp (ref "R241")
      (value "510")
      (footprint "RESC1005X40N")
      (description "Resistor - 1%")
      (fields
        (field (name "PART NUMBER") "R0402_510R_1%_0.0625W_100PPM")
        (field (name "POWER") "0.0625W")
        (field (name "AUTHOR") "CERN DEM JLC")
      )
      (libsource (lib "Resistors") (part "Resistor - 1%"))
    )
    (comp (ref "SW2")
      (value "Switch")
      (footprint "SW_OMRON_A6S-4102-H")
      (description "4 Ways SPST DIP Switch")
      (fields
        (field (name "PART NUMBER") "SW_OMRON_A6S-4102-H")
        (field (name "MANUFACTURER") "OMRON")
        (field (name "AUTHOR") "CERN DEM JMW")
      )
      (libsource (lib "Eletro-mechanical") (part "SW 4x SPST DIP Switch"))
    )
    (comp (ref "SW3")
      (value "Switch")
      (footprint "SW_OMRON_A6S-4102-H")
      (description "4 Ways SPST DIP Switch")
      (fields
        (field (name "PART NUMBER") "SW_OMRON_A6S-4102-H")
        (field (name "MANUFACTURER") "OMRON")
        (field (name "AUTHOR") "CERN DEM JMW")
      )
      (libsource (lib "Eletro-mechanical") (part "SW 4x SPST DIP Switch"))
    )
    (comp (ref "SW9")
      (value "Switch")
      (footprint "SW_OMRON_A6S-2102-H")
      (description "2 Ways SPST DIP Switch")
      (fields
        (field (name "PART NUMBER") "SW_OMRON_A6S-2102-H")
        (field (name "MANUFACTURER") "OMRON")
        (field (name "AUTHOR") "CERN DEM JMW")
      )
      (libsource (lib "Eletro-mechanical") (part "SW 2x SPST DIP Switch"))
    )
    (comp (ref "T10")
      (value "BSS138LT1G")
      (footprint "SOT95P240X110-3N")
      (description "N-CHANNEL MOSFET WITH DIODE")
      (fields (field (name "MANUFACTURER") "ON SEMICONDUCTOR") (field (name "AUTHOR") "CERN DEM JLC"))
      (libsource (lib "ICs And Semiconductors") (part "N-MOSFET-D 1G 2S 3D"))
    )
    (comp (ref "T11")
      (value "BSS138LT1G")
      (footprint "SOT95P240X110-3N")
      (description "N-CHANNEL MOSFET WITH DIODE")
      (fields (field (name "MANUFACTURER") "ON SEMICONDUCTOR") (field (name "AUTHOR") "CERN DEM JLC"))
      (libsource (lib "ICs And Semiconductors") (part "N-MOSFET-D 1G 2S 3D"))
    )
    (comp (ref "T12")
      (value "BSS138LT1G")
      (footprint "SOT95P240X110-3N")
      (description "N-CHANNEL MOSFET WITH DIODE")
      (fields (field (name "MANUFACTURER") "ON SEMICONDUCTOR") (field (name "AUTHOR") "CERN DEM JLC"))
      (libsource (lib "ICs And Semiconductors") (part "N-MOSFET-D 1G 2S 3D"))
    )
    (comp (ref "T13")
      (value "BSS138LT1G")
      (footprint "SOT95P240X110-3N")
      (description "N-CHANNEL MOSFET WITH DIODE")
      (fields (field (name "MANUFACTURER") "ON SEMICONDUCTOR") (field (name "AUTHOR") "CERN DEM JLC"))
      (libsource (lib "ICs And Semiconductors") (part "N-MOSFET-D 1G 2S 3D"))
    )
    (comp (ref "T14")
      (value "BSS138LT1G")
      (footprint "SOT95P240X110-3N")
      (description "N-CHANNEL MOSFET WITH DIODE")
      (fields (field (name "MANUFACTURER") "ON SEMICONDUCTOR") (field (name "AUTHOR") "CERN DEM JLC"))
      (libsource (lib "ICs And Semiconductors") (part "N-MOSFET-D 1G 2S 3D"))
    )
    (comp (ref "T15")
      (value "BSS138LT1G")
      (footprint "SOT95P240X110-3N")
      (description "N-CHANNEL MOSFET WITH DIODE")
      (fields (field (name "MANUFACTURER") "ON SEMICONDUCTOR") (field (name "AUTHOR") "CERN DEM JLC"))
      (libsource (lib "ICs And Semiconductors") (part "N-MOSFET-D 1G 2S 3D"))
    )
    (comp (ref "T16")
      (value "BSS138LT1G")
      (footprint "SOT95P240X110-3N")
      (description "N-CHANNEL MOSFET WITH DIODE")
      (fields (field (name "MANUFACTURER") "ON SEMICONDUCTOR") (field (name "AUTHOR") "CERN DEM JLC"))
      (libsource (lib "ICs And Semiconductors") (part "N-MOSFET-D 1G 2S 3D"))
    )
    (comp (ref "T17")
      (value "BSS138LT1G")
      (footprint "SOT95P240X110-3N")
      (description "N-CHANNEL MOSFET WITH DIODE")
      (fields (field (name "MANUFACTURER") "ON SEMICONDUCTOR") (field (name "AUTHOR") "CERN DEM JLC"))
      (libsource (lib "ICs And Semiconductors") (part "N-MOSFET-D 1G 2S 3D"))
    )
    (comp (ref "T26")
      (value "BSS138LT1G")
      (footprint "SOT95P240X110-3N")
      (description "N-CHANNEL MOSFET WITH DIODE")
      (fields (field (name "MANUFACTURER") "ON SEMICONDUCTOR") (field (name "AUTHOR") "CERN DEM JLC"))
      (libsource (lib "ICs And Semiconductors") (part "N-MOSFET-D 1G 2S 3D"))
    )
    (comp (ref "T27")
      (value "BSS138LT1G")
      (footprint "SOT95P240X110-3N")
      (description "N-CHANNEL MOSFET WITH DIODE")
      (fields (field (name "MANUFACTURER") "ON SEMICONDUCTOR") (field (name "AUTHOR") "CERN DEM JLC"))
      (libsource (lib "ICs And Semiconductors") (part "N-MOSFET-D 1G 2S 3D"))
    )
    (comp (ref "T28")
      (value "BSS138LT1G")
      (footprint "SOT95P240X110-3N")
      (description "N-CHANNEL MOSFET WITH DIODE")
      (fields (field (name "MANUFACTURER") "ON SEMICONDUCTOR") (field (name "AUTHOR") "CERN DEM JLC"))
      (libsource (lib "ICs And Semiconductors") (part "N-MOSFET-D 1G 2S 3D"))
    )
    (comp (ref "T29")
      (value "BSS138LT1G")
      (footprint "SOT95P240X110-3N")
      (description "N-CHANNEL MOSFET WITH DIODE")
      (fields (field (name "MANUFACTURER") "ON SEMICONDUCTOR") (field (name "AUTHOR") "CERN DEM JLC"))
      (libsource (lib "ICs And Semiconductors") (part "N-MOSFET-D 1G 2S 3D"))
    )
  )
  (nets
    (net (code "1") (name "/DIR_CTRL1") (class "Default")
      (node (ref "IC41") (pin "1") (pinfunction "1DE_1") (pintype "input"))
      (node (ref "IC41") (pin "12") (pinfunction "4DE_12") (pintype "input"))
      (node (ref "IC41") (pin "19") (pinfunction "~{3RE}_19") (pintype "input"))
      (node (ref "IC41") (pin "21") (pinfunction "~{4RE}_21") (pintype "input"))
      (node (ref "IC41") (pin "40") (pinfunction "~{1RE}_40") (pintype "input"))
      (node (ref "IC41") (pin "42") (pinfunction "~{2RE}_42") (pintype "input"))
      (node (ref "IC41") (pin "5") (pinfunction "2DE_5") (pintype "input"))
      (node (ref "IC41") (pin "8") (pinfunction "3DE_8") (pintype "input"))
      (node (ref "IC42") (pin "4") (pinfunction "P0_4") (pintype "bidirectional"))
      (node (ref "IC42") (pin "5") (pinfunction "P1_5") (pintype "bidirectional"))
      (node (ref "IC42") (pin "6") (pinfunction "P2_6") (pintype "bidirectional"))
      (node (ref "IC42") (pin "7") (pinfunction "P3_7") (pintype "bidirectional"))
      (node (ref "R197") (pin "1") (pinfunction "1_1") (pintype "passive"))
      (node (ref "SW9") (pin "1") (pinfunction "1_1") (pintype "passive"))
      (node (ref "T26") (pin "1") (pinfunction "G_1") (pintype "passive"))
    )
    (net (code "2") (name "/DIR_CTRL2") (class "Default")
      (node (ref "IC42") (pin "10") (pinfunction "P5_10") (pintype "bidirectional"))
      (node (ref "IC42") (pin "11") (pinfunction "P6_11") (pintype "bidirectional"))
      (node (ref "IC42") (pin "12") (pinfunction "P7_12") (pintype "bidirectional"))
      (node (ref "IC42") (pin "9") (pinfunction "P4_9") (pintype "bidirectional"))
      (node (ref "IC47") (pin "1") (pinfunction "1DE_1") (pintype "input"))
      (node (ref "IC47") (pin "12") (pinfunction "4DE_12") (pintype "input"))
      (node (ref "IC47") (pin "19") (pinfunction "~{3RE}_19") (pintype "input"))
      (node (ref "IC47") (pin "21") (pinfunction "~{4RE}_21") (pintype "input"))
      (node (ref "IC47") (pin "40") (pinfunction "~{1RE}_40") (pintype "input"))
      (node (ref "IC47") (pin "42") (pinfunction "~{2RE}_42") (pintype "input"))
      (node (ref "IC47") (pin "5") (pinfunction "2DE_5") (pintype "input"))
      (node (ref "IC47") (pin "8") (pinfunction "3DE_8") (pintype "input"))
      (node (ref "R219") (pin "1") (pinfunction "1_1") (pintype "passive"))
      (node (ref "SW9") (pin "2") (pinfunction "2_2") (pintype "passive"))
      (node (ref "T28") (pin "1") (pinfunction "G_1") (pintype "passive"))
    )
    (net (code "3") (name "/I2C_SCL") (class "Default")
      (node (ref "B3") (pin "1") (pinfunction "1_1") (pintype "bidirectional"))
      (node (ref "IC42") (pin "14") (pinfunction "SCL_14") (pintype "input"))
      (node (ref "IC52") (pin "1") (pinfunction "SCL_1") (pintype "input"))
      (node (ref "J16") (pin "27") (pinfunction "27_27") (pintype "bidirectional"))
    )
    (net (code "4") (name "/I2C_SDA") (class "Default")
      (node (ref "B2") (pin "1") (pinfunction "1_1") (pintype "bidirectional"))
      (node (ref "IC42") (pin "15") (pinfunction "SDA_15") (pintype "bidirectional"))
      (node (ref "IC52") (pin "3") (pinfunction "SDA_3") (pintype "bidirectional"))
      (node (ref "J16") (pin "26") (pinfunction "26_26") (pintype "bidirectional"))
    )
    (net (code "5") (name "/IO0") (class "Default")
      (node (ref "J1") (pin "1") (pinfunction "1_1") (pintype "bidirectional"))
      (node (ref "R199") (pin "2") (pinfunction "2_2") (pintype "passive"))
      (node (ref "R4") (pin "1") (pinfunction "1_1") (pintype "passive"))
    )
    (net (code "6") (name "/IO1") (class "Default")
      (node (ref "J17") (pin "1") (pinfunction "1_1") (pintype "bidirectional"))
      (node (ref "R202") (pin "2") (pinfunction "2_2") (pintype "passive"))
      (node (ref "R5") (pin "1") (pinfunction "1_1") (pintype "passive"))
    )
    (net (code "7") (name "/IO2") (class "Default")
      (node (ref "J2") (pin "1") (pinfunction "1_1") (pintype "bidirectional"))
      (node (ref "R205") (pin "2") (pinfunction "2_2") (pintype "passive"))
      (node (ref "R8") (pin "1") (pinfunction "1_1") (pintype "passive"))
    )
    (net (code "8") (name "/IO3") (class "Default")
      (node (ref "J14") (pin "1") (pinfunction "1_1") (pintype "bidirectional"))
      (node (ref "R10") (pin "1") (pinfunction "1_1") (pintype "passive"))
      (node (ref "R208") (pin "2") (pinfunction "2_2") (pintype "passive"))
    )
    (net (code "9") (name "/IO4") (class "Default")
      (node (ref "J3") (pin "1") (pinfunction "1_1") (pintype "bidirectional"))
      (node (ref "R11") (pin "1") (pinfunction "1_1") (pintype "passive"))
      (node (ref "R223") (pin "2") (pinfunction "2_2") (pintype "passive"))
    )
    (net (code "10") (name "/IO5") (class "Default")
      (node (ref "J21") (pin "1") (pinfunction "1_1") (pintype "bidirectional"))
      (node (ref "R13") (pin "1") (pinfunction "1_1") (pintype "passive"))
      (node (ref "R225") (pin "2") (pinfunction "2_2") (pintype "passive"))
    )
    (net (code "11") (name "/IO6") (class "Default")
      (node (ref "J4") (pin "1") (pinfunction "1_1") (pintype "bidirectional"))
      (node (ref "R20") (pin "1") (pinfunction "1_1") (pintype "passive"))
      (node (ref "R228") (pin "2") (pinfunction "2_2") (pintype "passive"))
    )
    (net (code "12") (name "/IO7") (class "Default")
      (node (ref "J19") (pin "1") (pinfunction "1_1") (pintype "bidirectional"))
      (node (ref "R22") (pin "1") (pinfunction "1_1") (pintype "passive"))
      (node (ref "R232") (pin "2") (pinfunction "2_2") (pintype "passive"))
    )
    (net (code "13") (name "/LED0") (class "Default")
      (node (ref "LD10") (pin "4") (pinfunction "A_4") (pintype "passive"))
      (node (ref "R213") (pin "2") (pinfunction "2_2") (pintype "passive"))
    )
    (net (code "14") (name "/LED1") (class "Default")
      (node (ref "LD10") (pin "2") (pinfunction "A_2") (pintype "passive"))
      (node (ref "R214") (pin "2") (pinfunction "2_2") (pintype "passive"))
    )
    (net (code "15") (name "/LED2") (class "Default")
      (node (ref "LD9") (pin "4") (pinfunction "A_4") (pintype "passive"))
      (node (ref "R215") (pin "2") (pinfunction "2_2") (pintype "passive"))
    )
    (net (code "16") (name "/LED3") (class "Default")
      (node (ref "LD9") (pin "2") (pinfunction "A_2") (pintype "passive"))
      (node (ref "R216") (pin "2") (pinfunction "2_2") (pintype "passive"))
    )
    (net (code "17") (name "/LED4") (class "Default")
      (node (ref "LD13") (pin "4") (pinfunction "A_4") (pintype "passive"))
      (node (ref "R238") (pin "2") (pinfunction "2_2") (pintype "passive"))
    )
    (net (code "18") (name "/LED5") (class "Default")
      (node (ref "LD13") (pin "2") (pinfunction "A_2") (pintype "passive"))
      (node (ref "R239") (pin "2") (pinfunction "2_2") (pintype "passive"))
    )
    (net (code "19") (name "/LED6") (class "Default")
      (node (ref "LD12") (pin "4") (pinfunction "A_4") (pintype "passive"))
      (node (ref "R240") (pin "2") (pinfunction "2_2") (pintype "passive"))
    )
    (net (code "20") (name "/LED7") (class "Default")
      (node (ref "LD12") (pin "2") (pinfunction "A_2") (pintype "passive"))
      (node (ref "R241") (pin "2") (pinfunction "2_2") (pintype "passive"))
    )
    (net (code "21") (name "/LED_OUT1") (class "Default")
      (node (ref "IC43") (pin "6") (pinfunction "A5_6") (pintype "output"))
      (node (ref "LD8") (pin "3") (pinfunction "C_3") (pintype "passive"))
      (node (ref "R17") (pin "1") (pinfunction "1_1") (pintype "passive"))
      (node (ref "R194") (pin "1") (pinfunction "1_1") (pintype "passive"))
      (node (ref "T27") (pin "1") (pinfunction "G_1") (pintype "passive"))
    )
    (net (code "22") (name "/LED_OUT2") (class "Default")
      (node (ref "IC48") (pin "6") (pinfunction "A5_6") (pintype "output"))
      (node (ref "LD11") (pin "3") (pinfunction "C_3") (pintype "passive"))
      (node (ref "R217") (pin "1") (pinfunction "1_1") (pintype "passive"))
      (node (ref "R23") (pin "1") (pinfunction "1_1") (pintype "passive"))
      (node (ref "T29") (pin "1") (pinfunction "G_1") (pintype "passive"))
    )
    (net (code "23") (name "/LVDS0_N") (class "Default")
      (node (ref "IC41") (pin "48") (pinfunction "1B_48") (pintype "bidirectional"))
      (node (ref "J16") (pin "3") (pinfunction "3_3") (pintype "bidirectional"))
      (node (ref "R201") (pin "2") (pinfunction "2_2") (pintype "passive"))
    )
    (net (code "24") (name "/LVDS0_P") (class "Default")
      (node (ref "IC41") (pin "47") (pinfunction "1A_47") (pintype "bidirectional"))
      (node (ref "J16") (pin "2") (pinfunction "2_2") (pintype "bidirectional"))
      (node (ref "R201") (pin "1") (pinfunction "1_1") (pintype "passive"))
    )
    (net (code "25") (name "/LVDS1_N") (class "Default")
      (node (ref "IC41") (pin "4") (pinfunction "2B_4") (pintype "bidirectional"))
      (node (ref "J16") (pin "6") (pinfunction "6_6") (pintype "bidirectional"))
      (node (ref "R204") (pin "2") (pinfunction "2_2") (pintype "passive"))
    )
    (net (code "26") (name "/LVDS1_P") (class "Default")
      (node (ref "IC41") (pin "3") (pinfunction "2A_3") (pintype "bidirectional"))
      (node (ref "J16") (pin "5") (pinfunction "5_5") (pintype "bidirectional"))
      (node (ref "R204") (pin "1") (pinfunction "1_1") (pintype "passive"))
    )
    (net (code "27") (name "/LVDS2_N") (class "Default")
      (node (ref "IC41") (pin "10") (pinfunction "3B_10") (pintype "bidirectional"))
      (node (ref "J16") (pin "9") (pinfunction "9_9") (pintype "bidirectional"))
      (node (ref "R207") (pin "2") (pinfunction "2_2") (pintype "passive"))
    )
    (net (code "28") (name "/LVDS2_P") (class "Default")
      (node (ref "IC41") (pin "9") (pinfunction "3A_9") (pintype "bidirectional"))
      (node (ref "J16") (pin "8") (pinfunction "8_8") (pintype "bidirectional"))
      (node (ref "R207") (pin "1") (pinfunction "1_1") (pintype "passive"))
    )
    (net (code "29") (name "/LVDS3_N") (class "Default")
      (node (ref "IC41") (pin "14") (pinfunction "4B_14") (pintype "bidirectional"))
      (node (ref "J16") (pin "12") (pinfunction "12_12") (pintype "bidirectional"))
      (node (ref "R211") (pin "2") (pinfunction "2_2") (pintype "passive"))
    )
    (net (code "30") (name "/LVDS3_P") (class "Default")
      (node (ref "IC41") (pin "13") (pinfunction "4A_13") (pintype "bidirectional"))
      (node (ref "J16") (pin "11") (pinfunction "11_11") (pintype "bidirectional"))
      (node (ref "R211") (pin "1") (pinfunction "1_1") (pintype "passive"))
    )
    (net (code "31") (name "/LVDS4_N") (class "Default")
      (node (ref "IC47") (pin "48") (pinfunction "1B_48") (pintype "bidirectional"))
      (node (ref "J16") (pin "15") (pinfunction "15_15") (pintype "bidirectional"))
      (node (ref "R224") (pin "2") (pinfunction "2_2") (pintype "passive"))
    )
    (net (code "32") (name "/LVDS4_P") (class "Default")
      (node (ref "IC47") (pin "47") (pinfunction "1A_47") (pintype "bidirectional"))
      (node (ref "J16") (pin "14") (pinfunction "14_14") (pintype "bidirectional"))
      (node (ref "R224") (pin "1") (pinfunction "1_1") (pintype "passive"))
    )
    (net (code "33") (name "/LVDS5_N") (class "Default")
      (node (ref "IC47") (pin "4") (pinfunction "2B_4") (pintype "bidirectional"))
      (node (ref "J16") (pin "18") (pinfunction "18_18") (pintype "bidirectional"))
      (node (ref "R227") (pin "2") (pinfunction "2_2") (pintype "passive"))
    )
    (net (code "34") (name "/LVDS5_P") (class "Default")
      (node (ref "IC47") (pin "3") (pinfunction "2A_3") (pintype "bidirectional"))
      (node (ref "J16") (pin "17") (pinfunction "17_17") (pintype "bidirectional"))
      (node (ref "R227") (pin "1") (pinfunction "1_1") (pintype "passive"))
    )
    (net (code "35") (name "/LVDS6_N") (class "Default")
      (node (ref "IC47") (pin "10") (pinfunction "3B_10") (pintype "bidirectional"))
      (node (ref "J16") (pin "21") (pinfunction "21_21") (pintype "bidirectional"))
      (node (ref "R230") (pin "2") (pinfunction "2_2") (pintype "passive"))
    )
    (net (code "36") (name "/LVDS6_P") (class "Default")
      (node (ref "IC47") (pin "9") (pinfunction "3A_9") (pintype "bidirectional"))
      (node (ref "J16") (pin "20") (pinfunction "20_20") (pintype "bidirectional"))
      (node (ref "R230") (pin "1") (pinfunction "1_1") (pintype "passive"))
    )
    (net (code "37") (name "/LVDS7_N") (class "Default")
      (node (ref "IC47") (pin "14") (pinfunction "4B_14") (pintype "bidirectional"))
      (node (ref "J16") (pin "24") (pinfunction "24_24") (pintype "bidirectional"))
      (node (ref "R234") (pin "2") (pinfunction "2_2") (pintype "passive"))
    )
    (net (code "38") (name "/LVDS7_P") (class "Default")
      (node (ref "IC47") (pin "13") (pinfunction "4A_13") (pintype "bidirectional"))
      (node (ref "J16") (pin "23") (pinfunction "23_23") (pintype "bidirectional"))
      (node (ref "R234") (pin "1") (pinfunction "1_1") (pintype "passive"))
    )
    (net (code "39") (name "/TERM_IO0") (class "Default")
      (node (ref "R213") (pin "1") (pinfunction "1_1") (pintype "passive"))
      (node (ref "SW3") (pin "8") (pinfunction "8_8") (pintype "passive"))
      (node (ref "T10") (pin "1") (pinfunction "G_1") (pintype "passive"))
    )
    (net (code "40") (name "/TERM_IO1") (class "Default")
      (node (ref "R214") (pin "1") (pinfunction "1_1") (pintype "passive"))
      (node (ref "SW3") (pin "7") (pinfunction "7_7") (pintype "passive"))
      (node (ref "T11") (pin "1") (pinfunction "G_1") (pintype "passive"))
    )
    (net (code "41") (name "/TERM_IO2") (class "Default")
      (node (ref "R215") (pin "1") (pinfunction "1_1") (pintype "passive"))
      (node (ref "SW3") (pin "6") (pinfunction "6_6") (pintype "passive"))
      (node (ref "T12") (pin "1") (pinfunction "G_1") (pintype "passive"))
    )
    (net (code "42") (name "/TERM_IO3") (class "Default")
      (node (ref "R216") (pin "1") (pinfunction "1_1") (pintype "passive"))
      (node (ref "SW3") (pin "5") (pinfunction "5_5") (pintype "passive"))
      (node (ref "T13") (pin "1") (pinfunction "G_1") (pintype "passive"))
    )
    (net (code "43") (name "/TERM_IO4") (class "Default")
      (node (ref "R238") (pin "1") (pinfunction "1_1") (pintype "passive"))
      (node (ref "SW2") (pin "8") (pinfunction "8_8") (pintype "passive"))
      (node (ref "T14") (pin "1") (pinfunction "G_1") (pintype "passive"))
    )
    (net (code "44") (name "/TERM_IO5") (class "Default")
      (node (ref "R239") (pin "1") (pinfunction "1_1") (pintype "passive"))
      (node (ref "SW2") (pin "7") (pinfunction "7_7") (pintype "passive"))
      (node (ref "T15") (pin "1") (pinfunction "G_1") (pintype "passive"))
    )
    (net (code "45") (name "/TERM_IO6") (class "Default")
      (node (ref "R240") (pin "1") (pinfunction "1_1") (pintype "passive"))
      (node (ref "SW2") (pin "6") (pinfunction "6_6") (pintype "passive"))
      (node (ref "T16") (pin "1") (pinfunction "G_1") (pintype "passive"))
    )
    (net (code "46") (name "/TERM_IO7") (class "Default")
      (node (ref "R241") (pin "1") (pinfunction "1_1") (pintype "passive"))
      (node (ref "SW2") (pin "5") (pinfunction "5_5") (pintype "passive"))
      (node (ref "T17") (pin "1") (pinfunction "G_1") (pintype "passive"))
    )
    (net (code "47") (name "GND") (class "Default")
      (node (ref "C163") (pin "1") (pinfunction "1_1") (pintype "passive"))
      (node (ref "C189") (pin "1") (pinfunction "1_1") (pintype "passive"))
      (node (ref "C190") (pin "1") (pinfunction "1_1") (pintype "passive"))
      (node (ref "C191") (pin "1") (pinfunction "1_1") (pintype "passive"))
      (node (ref "C192") (pin "1") (pinfunction "1_1") (pintype "passive"))
      (node (ref "C200") (pin "1") (pinfunction "1_1") (pintype "passive"))
      (node (ref "IC41") (pin "18") (pinfunction "GND_18") (pintype "power_in"))
      (node (ref "IC41") (pin "23") (pinfunction "GND_23") (pintype "power_in"))
      (node (ref "IC41") (pin "27") (pinfunction "GND_27") (pintype "power_in"))
      (node (ref "IC41") (pin "31") (pinfunction "GND_31") (pintype "power_in"))
      (node (ref "IC41") (pin "34") (pinfunction "GND_34") (pintype "power_in"))
      (node (ref "IC41") (pin "38") (pinfunction "GND_38") (pintype "power_in"))
      (node (ref "IC41") (pin "43") (pinfunction "GND_43") (pintype "power_in"))
      (node (ref "IC41") (pin "49") (pinfunction "EP_49") (pintype "power_in"))
      (node (ref "IC41") (pin "6") (pinfunction "GND_6") (pintype "power_in"))
      (node (ref "IC41") (pin "7") (pinfunction "GND_7") (pintype "power_in"))
      (node (ref "IC42") (pin "1") (pinfunction "A0_1") (pintype "input"))
      (node (ref "IC42") (pin "8") (pinfunction "GND_8") (pintype "power_in"))
      (node (ref "IC43") (pin "9") (pinfunction "GND2_9") (pintype "power_in"))
      (node (ref "IC44") (pin "8") (pinfunction "GND1_8") (pintype "power_in"))
      (node (ref "IC47") (pin "18") (pinfunction "GND_18") (pintype "power_in"))
      (node (ref "IC47") (pin "23") (pinfunction "GND_23") (pintype "power_in"))
      (node (ref "IC47") (pin "27") (pinfunction "GND_27") (pintype "power_in"))
      (node (ref "IC47") (pin "31") (pinfunction "GND_31") (pintype "power_in"))
      (node (ref "IC47") (pin "34") (pinfunction "GND_34") (pintype "power_in"))
      (node (ref "IC47") (pin "38") (pinfunction "GND_38") (pintype "power_in"))
      (node (ref "IC47") (pin "43") (pinfunction "GND_43") (pintype "power_in"))
      (node (ref "IC47") (pin "49") (pinfunction "EP_49") (pintype "power_in"))
      (node (ref "IC47") (pin "6") (pinfunction "GND_6") (pintype "power_in"))
      (node (ref "IC47") (pin "7") (pinfunction "GND_7") (pintype "power_in"))
      (node (ref "IC48") (pin "9") (pinfunction "GND2_9") (pintype "power_in"))
      (node (ref "IC49") (pin "1") (pinfunction "PGND_1") (pintype "power_in"))
      (node (ref "IC49") (pin "11") (pinfunction "EP_11") (pintype "power_in"))
      (node (ref "IC49") (pin "6") (pinfunction "AGND_6") (pintype "power_in"))
      (node (ref "IC50") (pin "8") (pinfunction "GND1_8") (pintype "power_in"))
      (node (ref "IC52") (pin "2") (pinfunction "VSS_2") (pintype "power_in"))
      (node (ref "J16") (pin "1") (pinfunction "1_1") (pintype "bidirectional"))
      (node (ref "J16") (pin "10") (pinfunction "10_10") (pintype "bidirectional"))
      (node (ref "J16") (pin "13") (pinfunction "13_13") (pintype "bidirectional"))
      (node (ref "J16") (pin "16") (pinfunction "16_16") (pintype "bidirectional"))
      (node (ref "J16") (pin "19") (pinfunction "19_19") (pintype "bidirectional"))
      (node (ref "J16") (pin "22") (pinfunction "22_22") (pintype "bidirectional"))
      (node (ref "J16") (pin "25") (pinfunction "25_25") (pintype "bidirectional"))
      (node (ref "J16") (pin "4") (pinfunction "4_4") (pintype "bidirectional"))
      (node (ref "J16") (pin "7") (pinfunction "7_7") (pintype "bidirectional"))
      (node (ref "R198") (pin "2") (pinfunction "2_2") (pintype "passive"))
      (node (ref "R212") (pin "2") (pinfunction "2_2") (pintype "passive"))
      (node (ref "R221") (pin "2") (pinfunction "2_2") (pintype "passive"))
      (node (ref "R235") (pin "2") (pinfunction "2_2") (pintype "passive"))
      (node (ref "R237") (pin "1") (pinfunction "1_1") (pintype "passive"))
      (node (ref "SW9") (pin "3") (pinfunction "3_3") (pintype "passive"))
      (node (ref "SW9") (pin "4") (pinfunction "4_4") (pintype "passive"))
      (node (ref "T26") (pin "2") (pinfunction "S_2") (pintype "passive"))
      (node (ref "T28") (pin "2") (pinfunction "S_2") (pintype "passive"))
    )
    (net (code "48") (name "GND_ISO1") (class "Default")
      (node (ref "IC3") (pin "1") (pinfunction "VSS_1") (pintype "power_in"))
      (node (ref "IC43") (pin "8") (pinfunction "GND1_8") (pintype "power_in"))
      (node (ref "IC44") (pin "11") (pinfunction "B5_11") (pintype "input"))
      (node (ref "IC44") (pin "9") (pinfunction "GND2_9") (pintype "power_in"))
      (node (ref "IC45") (pin "11") (pinfunction "GND_11") (pintype "power_in"))
      (node (ref "IC45") (pin "2") (pinfunction "GND_2") (pintype "power_in"))
      (node (ref "IC45") (pin "5") (pinfunction "GND_5") (pintype "power_in"))
      (node (ref "IC45") (pin "8") (pinfunction "GND_8") (pintype "power_in"))
      (node (ref "J1") (pin "2") (pinfunction "2_2") (pintype "bidirectional"))
      (node (ref "J14") (pin "2") (pinfunction "2_2") (pintype "bidirectional"))
      (node (ref "J17") (pin "2") (pinfunction "2_2") (pintype "bidirectional"))
      (node (ref "J2") (pin "2") (pinfunction "2_2") (pintype "bidirectional"))
      (node (ref "LD10") (pin "1") (pinfunction "C_1") (pintype "passive"))
      (node (ref "LD10") (pin "3") (pinfunction "C_3") (pintype "passive"))
      (node (ref "LD8") (pin "1") (pinfunction "C_1") (pintype "passive"))
      (node (ref "LD9") (pin "1") (pinfunction "C_1") (pintype "passive"))
      (node (ref "LD9") (pin "3") (pinfunction "C_3") (pintype "passive"))
      (node (ref "R12") (pin "1") (pinfunction "1_1") (pintype "passive"))
      (node (ref "R200") (pin "1") (pinfunction "1_1") (pintype "passive"))
      (node (ref "R203") (pin "1") (pinfunction "1_1") (pintype "passive"))
      (node (ref "R206") (pin "1") (pinfunction "1_1") (pintype "passive"))
      (node (ref "R209") (pin "1") (pinfunction "1_1") (pintype "passive"))
      (node (ref "T10") (pin "2") (pinfunction "S_2") (pintype "passive"))
      (node (ref "T11") (pin "2") (pinfunction "S_2") (pintype "passive"))
      (node (ref "T12") (pin "2") (pinfunction "S_2") (pintype "passive"))
      (node (ref "T13") (pin "2") (pinfunction "S_2") (pintype "passive"))
      (node (ref "T27") (pin "2") (pinfunction "S_2") (pintype "passive"))
    )
    (net (code "49") (name "GND_ISO2") (class "Default")
      (node (ref "IC4") (pin "1") (pinfunction "VSS_1") (pintype "power_in"))
      (node (ref "IC48") (pin "8") (pinfunction "GND1_8") (pintype "power_in"))
      (node (ref "IC50") (pin "11") (pinfunction "B5_11") (pintype "input"))
      (node (ref "IC50") (pin "9") (pinfunction "GND2_9") (pintype "power_in"))
      (node (ref "IC51") (pin "11") (pinfunction "GND_11") (pintype "power_in"))
      (node (ref "IC51") (pin "2") (pinfunction "GND_2") (pintype "power_in"))
      (node (ref "IC51") (pin "5") (pinfunction "GND_5") (pintype "power_in"))
      (node (ref "IC51") (pin "8") (pinfunction "GND_8") (pintype "power_in"))
      (node (ref "J19") (pin "2") (pinfunction "2_2") (pintype "bidirectional"))
      (node (ref "J21") (pin "2") (pinfunction "2_2") (pintype "bidirectional"))
      (node (ref "J3") (pin "2") (pinfunction "2_2") (pintype "bidirectional"))
      (node (ref "J4") (pin "2") (pinfunction "2_2") (pintype "bidirectional"))
      (node (ref "LD11") (pin "1") (pinfunction "C_1") (pintype "passive"))
      (node (ref "LD12") (pin "1") (pinfunction "C_1") (pintype "passive"))
      (node (ref "LD12") (pin "3") (pinfunction "C_3") (pintype "passive"))
      (node (ref "LD13") (pin "1") (pinfunction "C_1") (pintype "passive"))
      (node (ref "LD13") (pin "3") (pinfunction "C_3") (pintype "passive"))
      (node (ref "R19") (pin "1") (pinfunction "1_1") (pintype "passive"))
      (node (ref "R222") (pin "1") (pinfunction "1_1") (pintype "passive"))
      (node (ref "R226") (pin "1") (pinfunction "1_1") (pintype "passive"))
      (node (ref "R229") (pin "1") (pinfunction "1_1") (pintype "passive"))
      (node (ref "R233") (pin "1") (pinfunction "1_1") (pintype "passive"))
      (node (ref "T14") (pin "2") (pinfunction "S_2") (pintype "passive"))
      (node (ref "T15") (pin "2") (pinfunction "S_2") (pintype "passive"))
      (node (ref "T16") (pin "2") (pinfunction "S_2") (pintype "passive"))
      (node (ref "T17") (pin "2") (pinfunction "S_2") (pintype "passive"))
      (node (ref "T29") (pin "2") (pinfunction "S_2") (pintype "passive"))
    )
    (net (code "50") (name "Net-(IC3-RST)") (class "Default")
      (node (ref "IC3") (pin "2") (pinfunction "RST_2") (pintype "output"))
      (node (ref "IC45") (pin "13") (pinfunction "OE_13") (pintype "input"))
      (node (ref "R12") (pin "2") (pinfunction "2_2") (pintype "passive"))
    )
    (net (code "51") (name "Net-(IC4-RST)") (class "Default")
      (node (ref "IC4") (pin "2") (pinfunction "RST_2") (pintype "output"))
      (node (ref "IC51") (pin "13") (pinfunction "OE_13") (pintype "input"))
      (node (ref "R19") (pin "2") (pinfunction "2_2") (pintype "passive"))
    )
    (net (code "52") (name "Net-(IC41-1D)") (class "Default")
      (node (ref "IC41") (pin "35") (pinfunction "1D_35") (pintype "input"))
      (node (ref "IC43") (pin "15") (pinfunction "B1_15") (pintype "output"))
    )
    (net (code "53") (name "Net-(IC41-1FSEN)") (class "Default")
      (node (ref "IC41") (pin "20") (pinfunction "3FSEN_20") (pintype "input"))
      (node (ref "IC41") (pin "22") (pinfunction "4FSEN_22") (pintype "input"))
      (node (ref "IC41") (pin "39") (pinfunction "1FSEN_39") (pintype "input"))
      (node (ref "IC41") (pin "41") (pinfunction "2FSEN_41") (pintype "input"))
      (node (ref "R198") (pin "1") (pinfunction "1_1") (pintype "passive"))
      (node (ref "R212") (pin "1") (pinfunction "1_1") (pintype "passive"))
    )
    (net (code "54") (name "Net-(IC41-1R)") (class "Default")
      (node (ref "IC41") (pin "36") (pinfunction "1R_36") (pintype "output"))
      (node (ref "IC44") (pin "2") (pinfunction "A1_2") (pintype "input"))
    )
    (net (code "55") (name "Net-(IC41-2D)") (class "Default")
      (node (ref "IC41") (pin "32") (pinfunction "2D_32") (pintype "input"))
      (node (ref "IC43") (pin "14") (pinfunction "B2_14") (pintype "output"))
    )
    (net (code "56") (name "Net-(IC41-2R)") (class "Default")
      (node (ref "IC41") (pin "33") (pinfunction "2R_33") (pintype "output"))
      (node (ref "IC44") (pin "3") (pinfunction "A2_3") (pintype "input"))
    )
    (net (code "57") (name "Net-(IC41-3D)") (class "Default")
      (node (ref "IC41") (pin "28") (pinfunction "3D_28") (pintype "input"))
      (node (ref "IC43") (pin "13") (pinfunction "B3_13") (pintype "output"))
    )
    (net (code "58") (name "Net-(IC41-3R)") (class "Default")
      (node (ref "IC41") (pin "29") (pinfunction "3R_29") (pintype "output"))
      (node (ref "IC44") (pin "4") (pinfunction "A3_4") (pintype "input"))
    )
    (net (code "59") (name "Net-(IC41-4D)") (class "Default")
      (node (ref "IC41") (pin "25") (pinfunction "4D_25") (pintype "input"))
      (node (ref "IC43") (pin "12") (pinfunction "B4_12") (pintype "output"))
    )
    (net (code "60") (name "Net-(IC41-4R)") (class "Default")
      (node (ref "IC41") (pin "26") (pinfunction "4R_26") (pintype "output"))
      (node (ref "IC44") (pin "5") (pinfunction "A4_5") (pintype "input"))
    )
    (net (code "61") (name "Net-(IC43-A1)") (class "Default")
      (node (ref "IC43") (pin "2") (pinfunction "A1_2") (pintype "input"))
      (node (ref "IC44") (pin "15") (pinfunction "B1_15") (pintype "output"))
      (node (ref "R29") (pin "2") (pinfunction "2_2") (pintype "passive"))
    )
    (net (code "62") (name "Net-(IC43-A2)") (class "Default")
      (node (ref "IC43") (pin "3") (pinfunction "A2_3") (pintype "input"))
      (node (ref "IC44") (pin "14") (pinfunction "B2_14") (pintype "output"))
      (node (ref "R6") (pin "2") (pinfunction "2_2") (pintype "passive"))
    )
    (net (code "63") (name "Net-(IC43-A3)") (class "Default")
      (node (ref "IC43") (pin "4") (pinfunction "A3_4") (pintype "input"))
      (node (ref "IC44") (pin "13") (pinfunction "B3_13") (pintype "output"))
      (node (ref "R7") (pin "2") (pinfunction "2_2") (pintype "passive"))
    )
    (net (code "64") (name "Net-(IC43-A4)") (class "Default")
      (node (ref "IC43") (pin "5") (pinfunction "A4_5") (pintype "input"))
      (node (ref "IC44") (pin "12") (pinfunction "B4_12") (pintype "output"))
      (node (ref "R9") (pin "2") (pinfunction "2_2") (pintype "passive"))
    )
    (net (code "65") (name "Net-(IC43-B5)") (class "Default")
      (node (ref "IC43") (pin "11") (pinfunction "B5_11") (pintype "input"))
      (node (ref "R196") (pin "1") (pinfunction "1_1") (pintype "passive"))
      (node (ref "T26") (pin "3") (pinfunction "D_3") (pintype "passive"))
    )
    (net (code "66") (name "Net-(IC44-EN2)") (class "Default")
      (node (ref "IC44") (pin "10") (pinfunction "EN2_10") (pintype "input"))
      (node (ref "R17") (pin "2") (pinfunction "2_2") (pintype "passive"))
    )
    (net (code "67") (name "Net-(IC45-A1)") (class "Default")
      (node (ref "IC45") (pin "1") (pinfunction "A1_1") (pintype "bidirectional"))
      (node (ref "IC45") (pin "3") (pinfunction "A2_3") (pintype "bidirectional"))
      (node (ref "R10") (pin "2") (pinfunction "2_2") (pintype "passive"))
      (node (ref "R209") (pin "2") (pinfunction "2_2") (pintype "passive"))
    )
    (net (code "68") (name "Net-(IC45-A3)") (class "Default")
      (node (ref "IC45") (pin "4") (pinfunction "A3_4") (pintype "bidirectional"))
      (node (ref "IC45") (pin "6") (pinfunction "A4_6") (pintype "bidirectional"))
      (node (ref "R206") (pin "2") (pinfunction "2_2") (pintype "passive"))
      (node (ref "R8") (pin "2") (pinfunction "2_2") (pintype "passive"))
    )
    (net (code "69") (name "Net-(IC45-A5)") (class "Default")
      (node (ref "IC45") (pin "7") (pinfunction "A5_7") (pintype "bidirectional"))
      (node (ref "IC45") (pin "9") (pinfunction "A6_9") (pintype "bidirectional"))
      (node (ref "R203") (pin "2") (pinfunction "2_2") (pintype "passive"))
      (node (ref "R5") (pin "2") (pinfunction "2_2") (pintype "passive"))
    )
    (net (code "70") (name "Net-(IC45-A7)") (class "Default")
      (node (ref "IC45") (pin "10") (pinfunction "A7_10") (pintype "bidirectional"))
      (node (ref "IC45") (pin "12") (pinfunction "A8_12") (pintype "bidirectional"))
      (node (ref "R200") (pin "2") (pinfunction "2_2") (pintype "passive"))
      (node (ref "R4") (pin "2") (pinfunction "2_2") (pintype "passive"))
    )
    (net (code "71") (name "Net-(IC45-B1)") (class "Default")
      (node (ref "IC45") (pin "22") (pinfunction "B2_22") (pintype "bidirectional"))
      (node (ref "IC45") (pin "23") (pinfunction "B1_23") (pintype "bidirectional"))
      (node (ref "R9") (pin "1") (pinfunction "1_1") (pintype "passive"))
    )
    (net (code "72") (name "Net-(IC45-B3)") (class "Default")
      (node (ref "IC45") (pin "19") (pinfunction "B4_19") (pintype "bidirectional"))
      (node (ref "IC45") (pin "20") (pinfunction "B3_20") (pintype "bidirectional"))
      (node (ref "R7") (pin "1") (pinfunction "1_1") (pintype "passive"))
    )
    (net (code "73") (name "Net-(IC45-B5)") (class "Default")
      (node (ref "IC45") (pin "17") (pinfunction "B6_17") (pintype "bidirectional"))
      (node (ref "IC45") (pin "18") (pinfunction "B5_18") (pintype "bidirectional"))
      (node (ref "R6") (pin "1") (pinfunction "1_1") (pintype "passive"))
    )
    (net (code "74") (name "Net-(IC45-B7)") (class "Default")
      (node (ref "IC45") (pin "14") (pinfunction "B8_14") (pintype "bidirectional"))
      (node (ref "IC45") (pin "15") (pinfunction "B7_15") (pintype "bidirectional"))
      (node (ref "R29") (pin "1") (pinfunction "1_1") (pintype "passive"))
    )
    (net (code "75") (name "Net-(IC45-DIR)") (class "Default")
      (node (ref "IC45") (pin "24") (pinfunction "DIR_24") (pintype "input"))
      (node (ref "R210") (pin "1") (pinfunction "1_1") (pintype "passive"))
      (node (ref "T27") (pin "3") (pinfunction "D_3") (pintype "passive"))
    )
    (net (code "76") (name "Net-(IC47-1D)") (class "Default")
      (node (ref "IC47") (pin "35") (pinfunction "1D_35") (pintype "input"))
      (node (ref "IC48") (pin "15") (pinfunction "B1_15") (pintype "output"))
    )
    (net (code "77") (name "Net-(IC47-1FSEN)") (class "Default")
      (node (ref "IC47") (pin "20") (pinfunction "3FSEN_20") (pintype "input"))
      (node (ref "IC47") (pin "22") (pinfunction "4FSEN_22") (pintype "input"))
      (node (ref "IC47") (pin "39") (pinfunction "1FSEN_39") (pintype "input"))
      (node (ref "IC47") (pin "41") (pinfunction "2FSEN_41") (pintype "input"))
      (node (ref "R221") (pin "1") (pinfunction "1_1") (pintype "passive"))
      (node (ref "R235") (pin "1") (pinfunction "1_1") (pintype "passive"))
    )
    (net (code "78") (name "Net-(IC47-1R)") (class "Default")
      (node (ref "IC47") (pin "36") (pinfunction "1R_36") (pintype "output"))
      (node (ref "IC50") (pin "2") (pinfunction "A1_2") (pintype "input"))
    )
    (net (code "79") (name "Net-(IC47-2D)") (class "Default")
      (node (ref "IC47") (pin "32") (pinfunction "2D_32") (pintype "input"))
      (node (ref "IC48") (pin "14") (pinfunction "B2_14") (pintype "output"))
    )
    (net (code "80") (name "Net-(IC47-2R)") (class "Default")
      (node (ref "IC47") (pin "33") (pinfunction "2R_33") (pintype "output"))
      (node (ref "IC50") (pin "3") (pinfunction "A2_3") (pintype "input"))
    )
    (net (code "81") (name "Net-(IC47-3D)") (class "Default")
      (node (ref "IC47") (pin "28") (pinfunction "3D_28") (pintype "input"))
      (node (ref "IC48") (pin "13") (pinfunction "B3_13") (pintype "output"))
    )
    (net (code "82") (name "Net-(IC47-3R)") (class "Default")
      (node (ref "IC47") (pin "29") (pinfunction "3R_29") (pintype "output"))
      (node (ref "IC50") (pin "4") (pinfunction "A3_4") (pintype "input"))
    )
    (net (code "83") (name "Net-(IC47-4D)") (class "Default")
      (node (ref "IC47") (pin "25") (pinfunction "4D_25") (pintype "input"))
      (node (ref "IC48") (pin "12") (pinfunction "B4_12") (pintype "output"))
    )
    (net (code "84") (name "Net-(IC47-4R)") (class "Default")
      (node (ref "IC47") (pin "26") (pinfunction "4R_26") (pintype "output"))
      (node (ref "IC50") (pin "5") (pinfunction "A4_5") (pintype "input"))
    )
    (net (code "85") (name "Net-(IC48-A1)") (class "Default")
      (node (ref "IC48") (pin "2") (pinfunction "A1_2") (pintype "input"))
      (node (ref "IC50") (pin "15") (pinfunction "B1_15") (pintype "output"))
      (node (ref "R14") (pin "2") (pinfunction "2_2") (pintype "passive"))
    )
    (net (code "86") (name "Net-(IC48-A2)") (class "Default")
      (node (ref "IC48") (pin "3") (pinfunction "A2_3") (pintype "input"))
      (node (ref "IC50") (pin "14") (pinfunction "B2_14") (pintype "output"))
      (node (ref "R15") (pin "2") (pinfunction "2_2") (pintype "passive"))
    )
    (net (code "87") (name "Net-(IC48-A3)") (class "Default")
      (node (ref "IC48") (pin "4") (pinfunction "A3_4") (pintype "input"))
      (node (ref "IC50") (pin "13") (pinfunction "B3_13") (pintype "output"))
      (node (ref "R16") (pin "2") (pinfunction "2_2") (pintype "passive"))
    )
    (net (code "88") (name "Net-(IC48-A4)") (class "Default")
      (node (ref "IC48") (pin "5") (pinfunction "A4_5") (pintype "input"))
      (node (ref "IC50") (pin "12") (pinfunction "B4_12") (pintype "output"))
      (node (ref "R21") (pin "2") (pinfunction "2_2") (pintype "passive"))
    )
    (net (code "89") (name "Net-(IC48-B5)") (class "Default")
      (node (ref "IC48") (pin "11") (pinfunction "B5_11") (pintype "input"))
      (node (ref "R218") (pin "1") (pinfunction "1_1") (pintype "passive"))
      (node (ref "T28") (pin "3") (pinfunction "D_3") (pintype "passive"))
    )
    (net (code "90") (name "Net-(IC49-FB)") (class "Default")
      (node (ref "IC49") (pin "5") (pinfunction "FB_5") (pintype "input"))
      (node (ref "R231") (pin "1") (pinfunction "1_1") (pintype "passive"))
      (node (ref "R237") (pin "2") (pinfunction "2_2") (pintype "passive"))
    )
    (net (code "91") (name "Net-(IC49-SW)") (class "Default")
      (node (ref "IC49") (pin "9") (pinfunction "SW_9") (pintype "output"))
      (node (ref "L17") (pin "1") (pinfunction "1_1") (pintype "passive"))
    )
    (net (code "92") (name "Net-(IC50-EN2)") (class "Default")
      (node (ref "IC50") (pin "10") (pinfunction "EN2_10") (pintype "input"))
      (node (ref "R23") (pin "2") (pinfunction "2_2") (pintype "passive"))
    )
    (net (code "93") (name "Net-(IC51-A1)") (class "Default")
      (node (ref "IC51") (pin "1") (pinfunction "A1_1") (pintype "bidirectional"))
      (node (ref "IC51") (pin "3") (pinfunction "A2_3") (pintype "bidirectional"))
      (node (ref "R22") (pin "2") (pinfunction "2_2") (pintype "passive"))
      (node (ref "R233") (pin "2") (pinfunction "2_2") (pintype "passive"))
    )
    (net (code "94") (name "Net-(IC51-A3)") (class "Default")
      (node (ref "IC51") (pin "4") (pinfunction "A3_4") (pintype "bidirectional"))
      (node (ref "IC51") (pin "6") (pinfunction "A4_6") (pintype "bidirectional"))
      (node (ref "R20") (pin "2") (pinfunction "2_2") (pintype "passive"))
      (node (ref "R229") (pin "2") (pinfunction "2_2") (pintype "passive"))
    )
    (net (code "95") (name "Net-(IC51-A5)") (class "Default")
      (node (ref "IC51") (pin "7") (pinfunction "A5_7") (pintype "bidirectional"))
      (node (ref "IC51") (pin "9") (pinfunction "A6_9") (pintype "bidirectional"))
      (node (ref "R13") (pin "2") (pinfunction "2_2") (pintype "passive"))
      (node (ref "R226") (pin "2") (pinfunction "2_2") (pintype "passive"))
    )
    (net (code "96") (name "Net-(IC51-A7)") (class "Default")
      (node (ref "IC51") (pin "10") (pinfunction "A7_10") (pintype "bidirectional"))
      (node (ref "IC51") (pin "12") (pinfunction "A8_12") (pintype "bidirectional"))
      (node (ref "R11") (pin "2") (pinfunction "2_2") (pintype "passive"))
      (node (ref "R222") (pin "2") (pinfunction "2_2") (pintype "passive"))
    )
    (net (code "97") (name "Net-(IC51-B1)") (class "Default")
      (node (ref "IC51") (pin "22") (pinfunction "B2_22") (pintype "bidirectional"))
      (node (ref "IC51") (pin "23") (pinfunction "B1_23") (pintype "bidirectional"))
      (node (ref "R21") (pin "1") (pinfunction "1_1") (pintype "passive"))
    )
    (net (code "98") (name "Net-(IC51-B3)") (class "Default")
      (node (ref "IC51") (pin "19") (pinfunction "B4_19") (pintype "bidirectional"))
      (node (ref "IC51") (pin "20") (pinfunction "B3_20") (pintype "bidirectional"))
      (node (ref "R16") (pin "1") (pinfunction "1_1") (pintype "passive"))
    )
    (net (code "99") (name "Net-(IC51-B5)") (class "Default")
      (node (ref "IC51") (pin "17") (pinfunction "B6_17") (pintype "bidirectional"))
      (node (ref "IC51") (pin "18") (pinfunction "B5_18") (pintype "bidirectional"))
      (node (ref "R15") (pin "1") (pinfunction "1_1") (pintype "passive"))
    )
    (net (code "100") (name "Net-(IC51-B7)") (class "Default")
      (node (ref "IC51") (pin "14") (pinfunction "B8_14") (pintype "bidirectional"))
      (node (ref "IC51") (pin "15") (pinfunction "B7_15") (pintype "bidirectional"))
      (node (ref "R14") (pin "1") (pinfunction "1_1") (pintype "passive"))
    )
    (net (code "101") (name "Net-(IC51-DIR)") (class "Default")
      (node (ref "IC51") (pin "24") (pinfunction "DIR_24") (pintype "input"))
      (node (ref "R236") (pin "1") (pinfunction "1_1") (pintype "passive"))
      (node (ref "T29") (pin "3") (pinfunction "D_3") (pintype "passive"))
    )
    (net (code "102") (name "Net-(LD8A-A)") (class "Default")
      (node (ref "LD8") (pin "2") (pinfunction "A_2") (pintype "passive"))
      (node (ref "R194") (pin "2") (pinfunction "2_2") (pintype "passive"))
    )
    (net (code "103") (name "Net-(LD8B-A)") (class "Default")
      (node (ref "LD8") (pin "4") (pinfunction "A_4") (pintype "passive"))
      (node (ref "R195") (pin "2") (pinfunction "2_2") (pintype "passive"))
    )
    (net (code "104") (name "Net-(LD11A-A)") (class "Default")
      (node (ref "LD11") (pin "2") (pinfunction "A_2") (pintype "passive"))
      (node (ref "R217") (pin "2") (pinfunction "2_2") (pintype "passive"))
    )
    (net (code "105") (name "Net-(LD11B-A)") (class "Default")
      (node (ref "LD11") (pin "4") (pinfunction "A_4") (pintype "passive"))
      (node (ref "R220") (pin "2") (pinfunction "2_2") (pintype "passive"))
    )
    (net (code "106") (name "Net-(T10-D)") (class "Default")
      (node (ref "R199") (pin "1") (pinfunction "1_1") (pintype "passive"))
      (node (ref "T10") (pin "3") (pinfunction "D_3") (pintype "passive"))
    )
    (net (code "107") (name "Net-(T11-D)") (class "Default")
      (node (ref "R202") (pin "1") (pinfunction "1_1") (pintype "passive"))
      (node (ref "T11") (pin "3") (pinfunction "D_3") (pintype "passive"))
    )
    (net (code "108") (name "Net-(T12-D)") (class "Default")
      (node (ref "R205") (pin "1") (pinfunction "1_1") (pintype "passive"))
      (node (ref "T12") (pin "3") (pinfunction "D_3") (pintype "passive"))
    )
    (net (code "109") (name "Net-(T13-D)") (class "Default")
      (node (ref "R208") (pin "1") (pinfunction "1_1") (pintype "passive"))
      (node (ref "T13") (pin "3") (pinfunction "D_3") (pintype "passive"))
    )
    (net (code "110") (name "Net-(T14-D)") (class "Default")
      (node (ref "R223") (pin "1") (pinfunction "1_1") (pintype "passive"))
      (node (ref "T14") (pin "3") (pinfunction "D_3") (pintype "passive"))
    )
    (net (code "111") (name "Net-(T15-D)") (class "Default")
      (node (ref "R225") (pin "1") (pinfunction "1_1") (pintype "passive"))
      (node (ref "T15") (pin "3") (pinfunction "D_3") (pintype "passive"))
    )
    (net (code "112") (name "Net-(T16-D)") (class "Default")
      (node (ref "R228") (pin "1") (pinfunction "1_1") (pintype "passive"))
      (node (ref "T16") (pin "3") (pinfunction "D_3") (pintype "passive"))
    )
    (net (code "113") (name "Net-(T17-D)") (class "Default")
      (node (ref "R232") (pin "1") (pinfunction "1_1") (pintype "passive"))
      (node (ref "T17") (pin "3") (pinfunction "D_3") (pintype "passive"))
    )
    (net (code "114") (name "P3V3") (class "Default")
      (node (ref "C189") (pin "2") (pinfunction "2_2") (pintype "passive"))
      (node (ref "C190") (pin "2") (pinfunction "2_2") (pintype "passive"))
      (node (ref "IC41") (pin "11") (pinfunction "VCC_11") (pintype "power_in"))
      (node (ref "IC41") (pin "15") (pinfunction "VCC_15") (pintype "power_in"))
      (node (ref "IC41") (pin "16") (pinfunction "VCC_16") (pintype "power_in"))
      (node (ref "IC41") (pin "2") (pinfunction "VCC_2") (pintype "power_in"))
      (node (ref "IC41") (pin "24") (pinfunction "VCC_24") (pintype "power_in"))
      (node (ref "IC41") (pin "30") (pinfunction "PDN_30") (pintype "input"))
      (node (ref "IC41") (pin "37") (pinfunction "VCC_37") (pintype "power_in"))
      (node (ref "IC41") (pin "45") (pinfunction "VCC_45") (pintype "power_in"))
      (node (ref "IC41") (pin "46") (pinfunction "VCC_46") (pintype "power_in"))
      (node (ref "IC43") (pin "10") (pinfunction "EN2_10") (pintype "input"))
      (node (ref "IC43") (pin "16") (pinfunction "VDD2_16") (pintype "power_in"))
      (node (ref "IC44") (pin "1") (pinfunction "VDD1_1") (pintype "power_in"))
      (node (ref "IC44") (pin "7") (pinfunction "EN1_7") (pintype "input"))
      (node (ref "IC47") (pin "11") (pinfunction "VCC_11") (pintype "power_in"))
      (node (ref "IC47") (pin "15") (pinfunction "VCC_15") (pintype "power_in"))
      (node (ref "IC47") (pin "16") (pinfunction "VCC_16") (pintype "power_in"))
      (node (ref "IC47") (pin "2") (pinfunction "VCC_2") (pintype "power_in"))
      (node (ref "IC47") (pin "24") (pinfunction "VCC_24") (pintype "power_in"))
      (node (ref "IC47") (pin "30") (pinfunction "PDN_30") (pintype "input"))
      (node (ref "IC47") (pin "37") (pinfunction "VCC_37") (pintype "power_in"))
      (node (ref "IC47") (pin "45") (pinfunction "VCC_45") (pintype "power_in"))
      (node (ref "IC47") (pin "46") (pinfunction "VCC_46") (pintype "power_in"))
      (node (ref "IC48") (pin "10") (pinfunction "EN2_10") (pintype "input"))
      (node (ref "IC48") (pin "16") (pinfunction "VDD2_16") (pintype "power_in"))
      (node (ref "IC49") (pin "10") (pinfunction "VOS_10") (pintype "input"))
      (node (ref "IC49") (pin "8") (pinfunction "SLEEP_8") (pintype "input"))
      (node (ref "IC50") (pin "1") (pinfunction "VDD1_1") (pintype "power_in"))
      (node (ref "IC50") (pin "7") (pinfunction "EN1_7") (pintype "input"))
      (node (ref "L17") (pin "2") (pinfunction "2_2") (pintype "passive"))
      (node (ref "R196") (pin "2") (pinfunction "2_2") (pintype "passive"))
      (node (ref "R197") (pin "2") (pinfunction "2_2") (pintype "passive"))
      (node (ref "R218") (pin "2") (pinfunction "2_2") (pintype "passive"))
      (node (ref "R219") (pin "2") (pinfunction "2_2") (pintype "passive"))
      (node (ref "R231") (pin "2") (pinfunction "2_2") (pintype "passive"))
    )
    (net (code "115") (name "P3V3_MP") (class "Default")
      (node (ref "C163") (pin "2") (pinfunction "2_2") (pintype "passive"))
      (node (ref "C200") (pin "2") (pinfunction "2_2") (pintype "passive"))
      (node (ref "IC42") (pin "16") (pinfunction "VCC_16") (pintype "bidirectional"))
      (node (ref "IC42") (pin "2") (pinfunction "A1_2") (pintype "input"))
      (node (ref "IC42") (pin "3") (pinfunction "A2_3") (pintype "input"))
      (node (ref "IC52") (pin "4") (pinfunction "VCC_4") (pintype "power_in"))
      (node (ref "J16") (pin "30") (pinfunction "30_30") (pintype "bidirectional"))
    )
    (net (code "116") (name "P5V0_ISO1") (class "Default")
      (node (ref "IC3") (pin "3") (pinfunction "VDD_3") (pintype "power_in"))
      (node (ref "IC43") (pin "1") (pinfunction "VDD1_1") (pintype "power_in"))
      (node (ref "IC43") (pin "7") (pinfunction "EN1_7") (pintype "input"))
      (node (ref "IC44") (pin "16") (pinfunction "VDD2_16") (pintype "power_in"))
      (node (ref "IC45") (pin "16") (pinfunction "VCC_16") (pintype "power_in"))
      (node (ref "IC45") (pin "21") (pinfunction "VCC_21") (pintype "power_in"))
      (node (ref "R195") (pin "1") (pinfunction "1_1") (pintype "passive"))
      (node (ref "R210") (pin "2") (pinfunction "2_2") (pintype "passive"))
      (node (ref "SW3") (pin "1") (pinfunction "1_1") (pintype "passive"))
      (node (ref "SW3") (pin "2") (pinfunction "2_2") (pintype "passive"))
      (node (ref "SW3") (pin "3") (pinfunction "3_3") (pintype "passive"))
      (node (ref "SW3") (pin "4") (pinfunction "4_4") (pintype "passive"))
    )
    (net (code "117") (name "P5V0_ISO2") (class "Default")
      (node (ref "IC4") (pin "3") (pinfunction "VDD_3") (pintype "power_in"))
      (node (ref "IC48") (pin "1") (pinfunction "VDD1_1") (pintype "power_in"))
      (node (ref "IC48") (pin "7") (pinfunction "EN1_7") (pintype "input"))
      (node (ref "IC50") (pin "16") (pinfunction "VDD2_16") (pintype "power_in"))
      (node (ref "IC51") (pin "16") (pinfunction "VCC_16") (pintype "power_in"))
      (node (ref "IC51") (pin "21") (pinfunction "VCC_21") (pintype "power_in"))
      (node (ref "R220") (pin "1") (pinfunction "1_1") (pintype "passive"))
      (node (ref "R236") (pin "2") (pinfunction "2_2") (pintype "passive"))
      (node (ref "SW2") (pin "1") (pinfunction "1_1") (pintype "passive"))
      (node (ref "SW2") (pin "2") (pinfunction "2_2") (pintype "passive"))
      (node (ref "SW2") (pin "3") (pinfunction "3_3") (pintype "passive"))
      (node (ref "SW2") (pin "4") (pinfunction "4_4") (pintype "passive"))
    )
    (net (code "118") (name "P12V0") (class "Default")
      (node (ref "C191") (pin "2") (pinfunction "2_2") (pintype "passive"))
      (node (ref "C192") (pin "2") (pinfunction "2_2") (pintype "passive"))
      (node (ref "IC49") (pin "2") (pinfunction "VIN_2") (pintype "input"))
      (node (ref "IC49") (pin "3") (pinfunction "EN_3") (pintype "input"))
      (node (ref "J16") (pin "28") (pinfunction "28_28") (pintype "bidirectional"))
      (node (ref "J16") (pin "29") (pinfunction "29_29") (pintype "bidirectional"))
    )
    (net (code "119") (name "unconnected-(IC41-NC-Pad17)") (class "Default")
      (node (ref "IC41") (pin "17") (pinfunction "NC_17") (pintype "passive"))
    )
    (net (code "120") (name "unconnected-(IC41-NC-Pad44)") (class "Default")
      (node (ref "IC41") (pin "44") (pinfunction "NC_44") (pintype "passive"))
    )
    (net (code "121") (name "unconnected-(IC42-~{INT}-Pad13)") (class "Default")
      (node (ref "IC42") (pin "13") (pinfunction "~{INT}_13") (pintype "output"))
    )
    (net (code "122") (name "unconnected-(IC44-A5-Pad6)") (class "Default")
      (node (ref "IC44") (pin "6") (pinfunction "A5_6") (pintype "output"))
    )
    (net (code "123") (name "unconnected-(IC47-NC-Pad17)") (class "Default")
      (node (ref "IC47") (pin "17") (pinfunction "NC_17") (pintype "passive"))
    )
    (net (code "124") (name "unconnected-(IC47-NC-Pad44)") (class "Default")
      (node (ref "IC47") (pin "44") (pinfunction "NC_44") (pintype "passive"))
    )
    (net (code "125") (name "unconnected-(IC49-NC-Pad4)") (class "Default")
      (node (ref "IC49") (pin "4") (pinfunction "NC_4") (pintype "passive"))
    )
    (net (code "126") (name "unconnected-(IC49-PG-Pad7)") (class "Default")
      (node (ref "IC49") (pin "7") (pinfunction "PG_7") (pintype "output"))
    )
    (net (code "127") (name "unconnected-(IC50-A5-Pad6)") (class "Default")
      (node (ref "IC50") (pin "6") (pinfunction "A5_6") (pintype "output"))
    )
    (net (code "128") (name "unconnected-(IC52-NC-Pad5)") (class "Default")
      (node (ref "IC52") (pin "5") (pinfunction "NC_5") (pintype "passive"))
    )
  )
)
